# SoC_pwr_1.net
KiCad netlist of a schematic drawn in Altium Designer
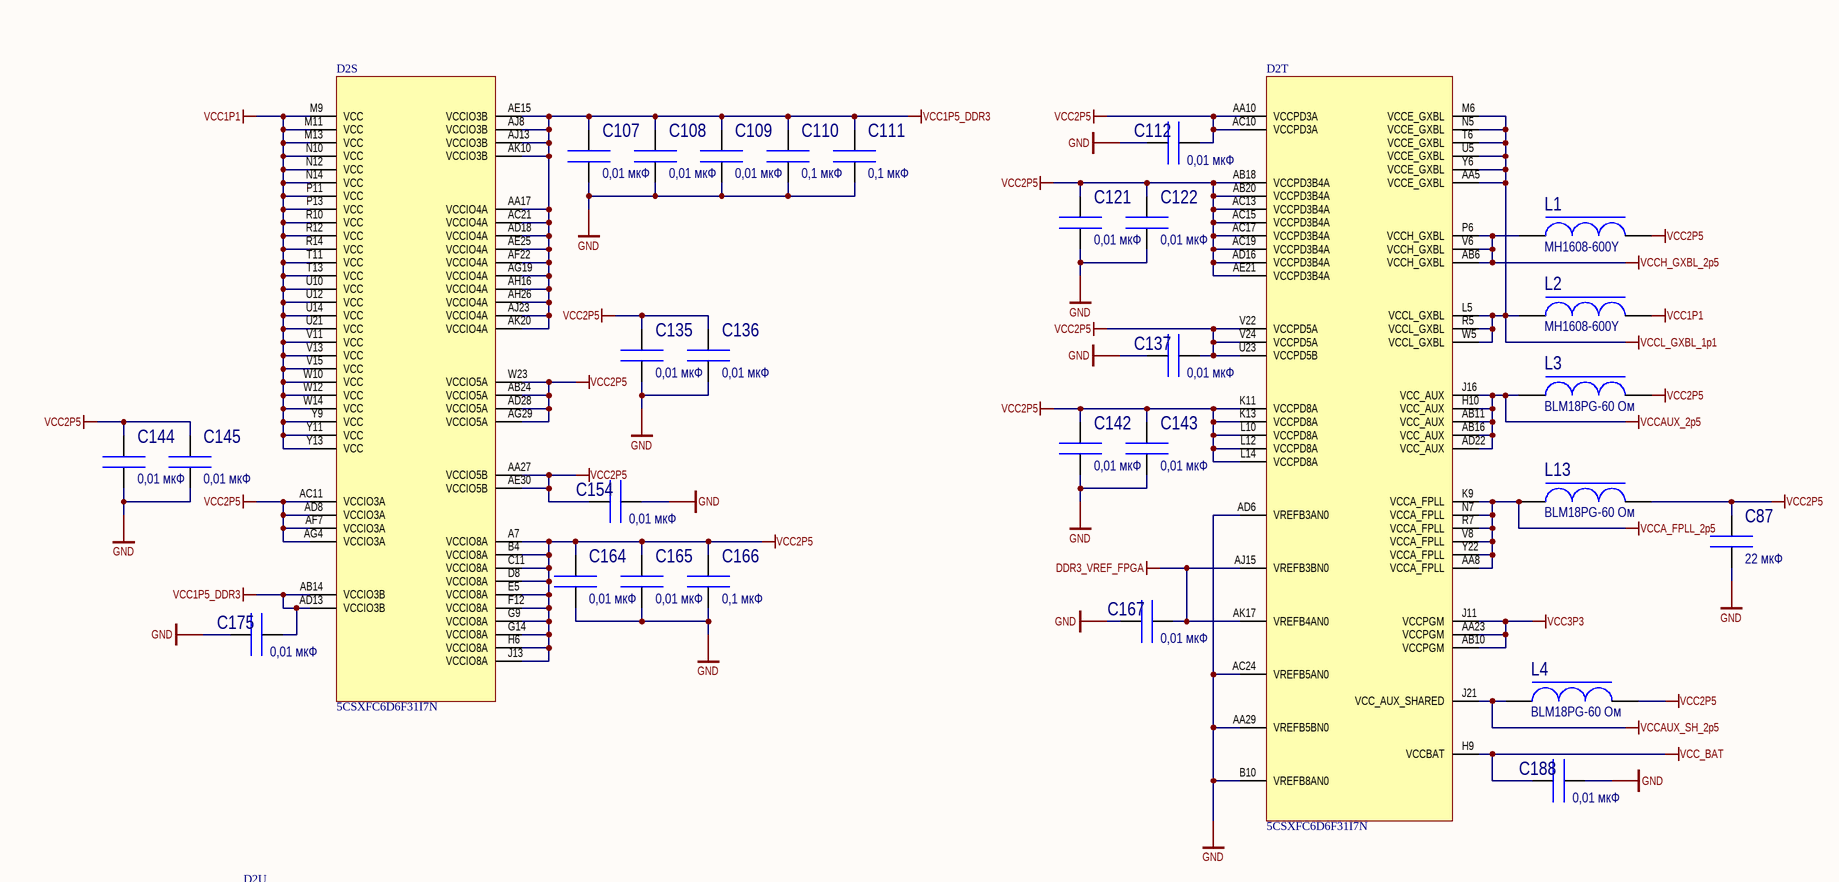
[diagram p0: SoC_pwr_1.SchDoc, top left]
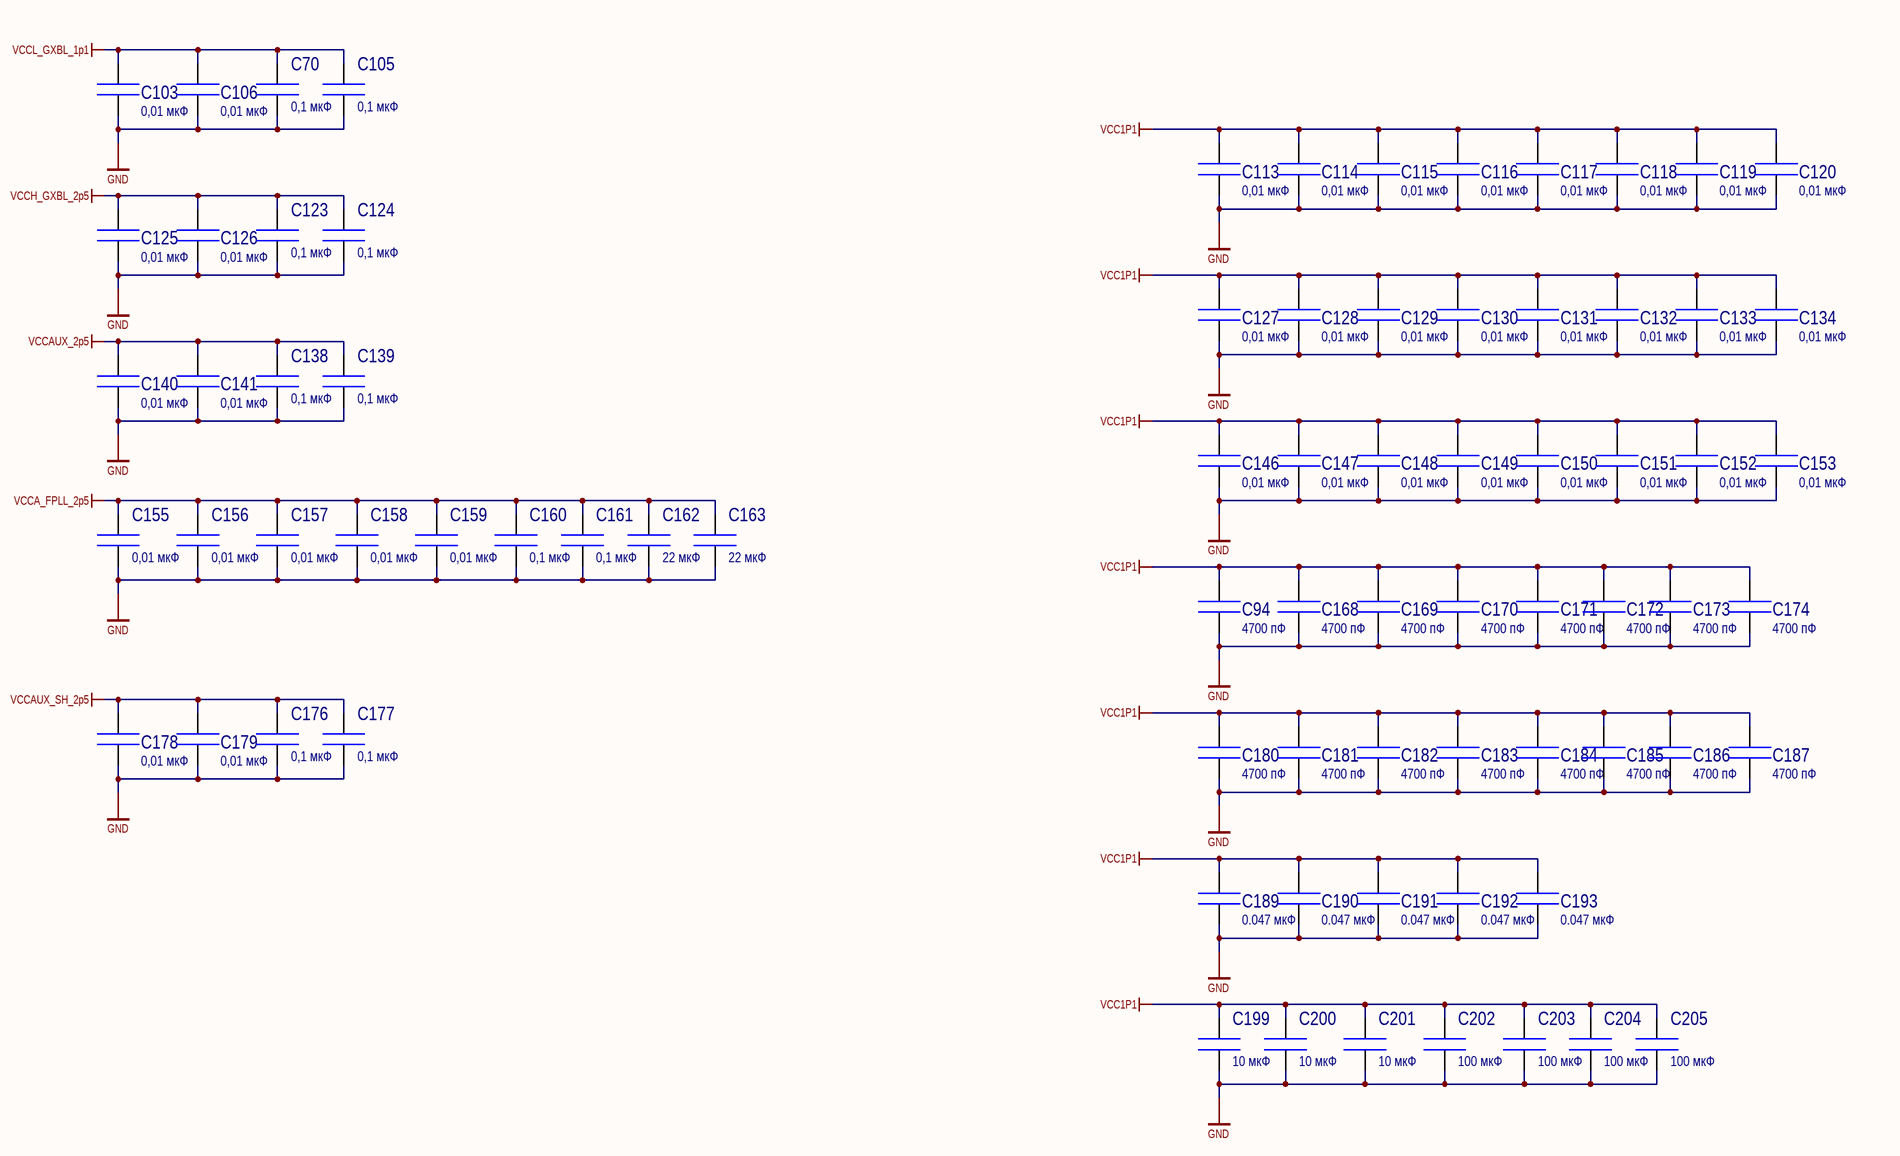
[diagram p1: SoC_pwr_1.SchDoc, top right]
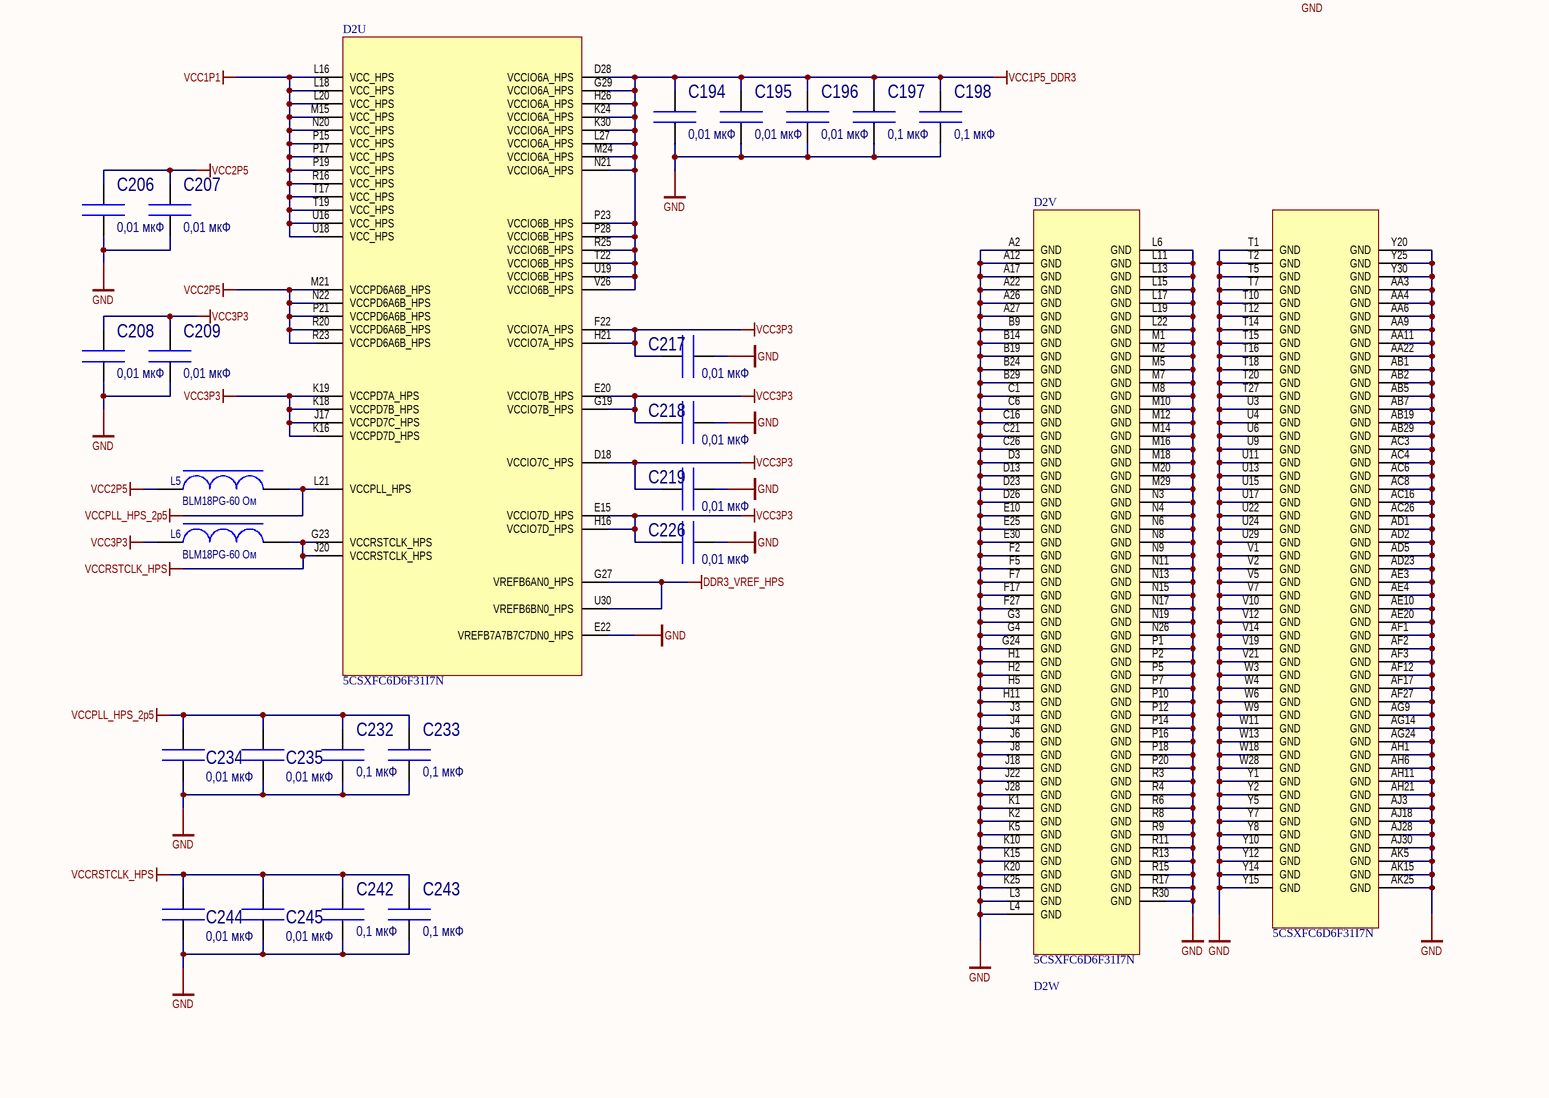
[diagram p2: SoC_pwr_1.SchDoc, bottom left]
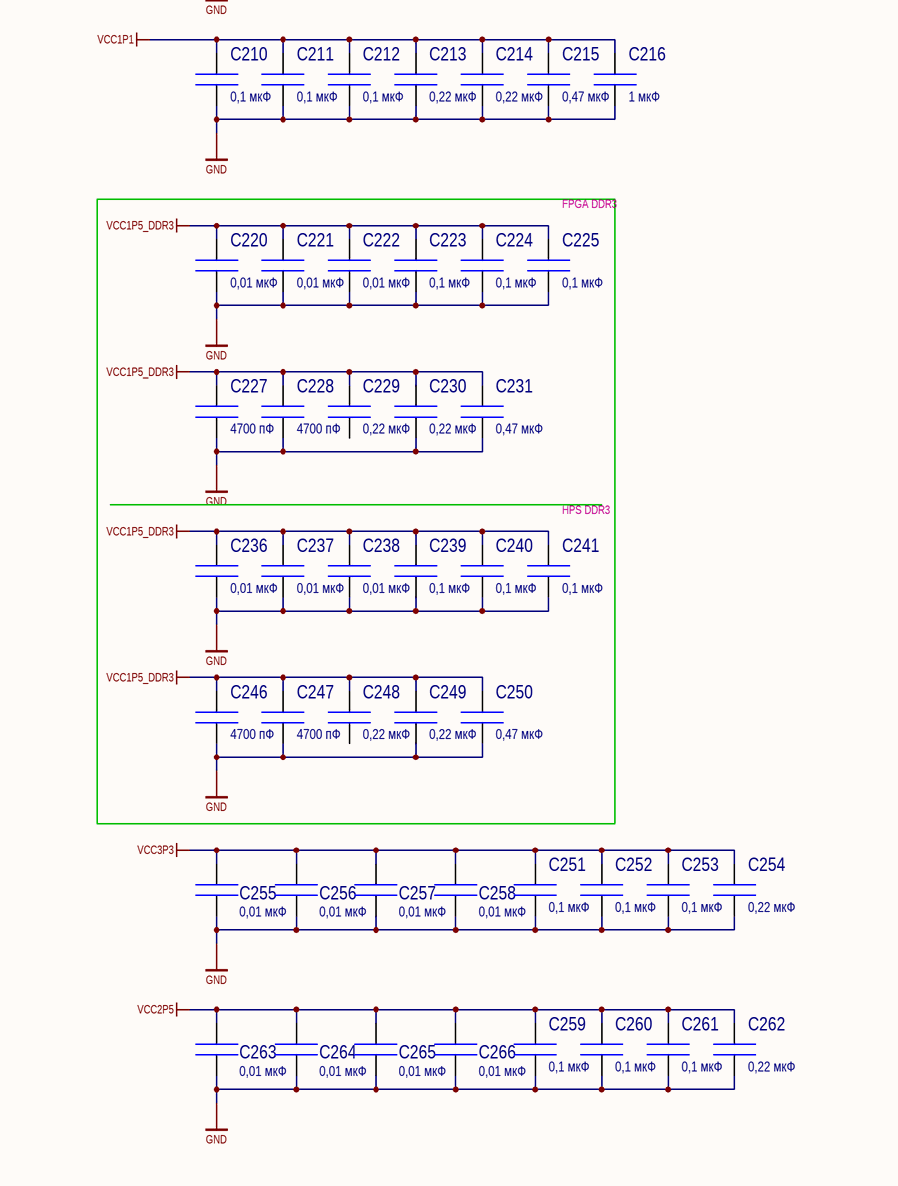
[diagram p3: SoC_pwr_1.SchDoc, bottom right]

(export (version "E")
  (design (tool "Eeschema 10.0.6"))
  (components
    (comp (ref "C70")
      (value "0,1 мкФ")
      (footprint "CC0402(1005)")
      (description "Чип конденсатор керамический")
      (fields (field (name "Comment") "CC0402-X7R-0,1 мкФ-20%-10В"))
      (libsource (lib "Чип конденсаторы") (part "CC0402-X7R-#-20%-10В"))
    )
    (comp (ref "C87")
      (value "22 мкФ")
      (footprint "CC0603")
      (description "Чип конденсатор керамический")
      (fields (field (name "Comment") "CC0603-X5R-22 мкФ-20%-6,3В"))
      (libsource (lib "Конденсаторы") (part "CC0603-X5R-#-20%-6,3В"))
    )
    (comp (ref "C94")
      (value "4700 пФ")
      (footprint "CC0402(1005)")
      (description "Чип конденсатор керамический")
      (fields (field (name "Comment") "CC0402-X7R-4700 пФ-10%-50В"))
      (libsource (lib "Чип конденсаторы") (part "CC0402-X7R-#-20%-10В"))
    )
    (comp (ref "C103")
      (value "0,01 мкФ")
      (footprint "CC0402(1005)")
      (description "Чип конденсатор керамический")
      (fields (field (name "Comment") "CC0402-X7R-0,01 мкФ-10%-50В"))
      (libsource (lib "Чип конденсаторы") (part "CC0402-X7R-#-20%-10В"))
    )
    (comp (ref "C105")
      (value "0,1 мкФ")
      (footprint "CC0402(1005)")
      (description "Чип конденсатор керамический")
      (fields (field (name "Comment") "CC0402-X7R-0,1 мкФ-20%-10В"))
      (libsource (lib "Чип конденсаторы") (part "CC0402-X7R-#-20%-10В"))
    )
    (comp (ref "C106")
      (value "0,01 мкФ")
      (footprint "CC0402(1005)")
      (description "Чип конденсатор керамический")
      (fields (field (name "Comment") "CC0402-X7R-0,01 мкФ-10%-50В"))
      (libsource (lib "Чип конденсаторы") (part "CC0402-X7R-#-20%-10В"))
    )
    (comp (ref "C107")
      (value "0,01 мкФ")
      (footprint "CC0402(1005)")
      (description "Чип конденсатор керамический")
      (fields (field (name "Comment") "CC0402-X7R-0,01 мкФ-10%-50В"))
      (libsource (lib "Чип конденсаторы") (part "CC0402-X7R-#-20%-10В"))
    )
    (comp (ref "C108")
      (value "0,01 мкФ")
      (footprint "CC0402(1005)")
      (description "Чип конденсатор керамический")
      (fields (field (name "Comment") "CC0402-X7R-0,01 мкФ-10%-50В"))
      (libsource (lib "Чип конденсаторы") (part "CC0402-X7R-#-20%-10В"))
    )
    (comp (ref "C109")
      (value "0,01 мкФ")
      (footprint "CC0402(1005)")
      (description "Чип конденсатор керамический")
      (fields (field (name "Comment") "CC0402-X7R-0,01 мкФ-10%-50В"))
      (libsource (lib "Чип конденсаторы") (part "CC0402-X7R-#-20%-10В"))
    )
    (comp (ref "C110")
      (value "0,1 мкФ")
      (footprint "CC0402(1005)")
      (description "Чип конденсатор керамический")
      (fields (field (name "Comment") "CC0402-X7R-0,1 мкФ-20%-10В"))
      (libsource (lib "Чип конденсаторы") (part "CC0402-X7R-#-20%-10В"))
    )
    (comp (ref "C111")
      (value "0,1 мкФ")
      (footprint "CC0402(1005)")
      (description "Чип конденсатор керамический")
      (fields (field (name "Comment") "CC0402-X7R-0,1 мкФ-20%-10В"))
      (libsource (lib "Чип конденсаторы") (part "CC0402-X7R-#-20%-10В"))
    )
    (comp (ref "C112")
      (value "0,01 мкФ")
      (footprint "CC0402(1005)")
      (description "Чип конденсатор керамический")
      (fields (field (name "Comment") "CC0402-X7R-0,01 мкФ-10%-50В"))
      (libsource (lib "Чип конденсаторы") (part "CC0402-X7R-#-20%-10В"))
    )
    (comp (ref "C113")
      (value "0,01 мкФ")
      (footprint "CC0402(1005)")
      (description "Чип конденсатор керамический")
      (fields (field (name "Comment") "CC0402-X7R-0,01 мкФ-10%-50В"))
      (libsource (lib "Чип конденсаторы") (part "CC0402-X7R-#-20%-10В"))
    )
    (comp (ref "C114")
      (value "0,01 мкФ")
      (footprint "CC0402(1005)")
      (description "Чип конденсатор керамический")
      (fields (field (name "Comment") "CC0402-X7R-0,01 мкФ-10%-50В"))
      (libsource (lib "Чип конденсаторы") (part "CC0402-X7R-#-20%-10В"))
    )
    (comp (ref "C115")
      (value "0,01 мкФ")
      (footprint "CC0402(1005)")
      (description "Чип конденсатор керамический")
      (fields (field (name "Comment") "CC0402-X7R-0,01 мкФ-10%-50В"))
      (libsource (lib "Чип конденсаторы") (part "CC0402-X7R-#-20%-10В"))
    )
    (comp (ref "C116")
      (value "0,01 мкФ")
      (footprint "CC0402(1005)")
      (description "Чип конденсатор керамический")
      (fields (field (name "Comment") "CC0402-X7R-0,01 мкФ-10%-50В"))
      (libsource (lib "Чип конденсаторы") (part "CC0402-X7R-#-20%-10В"))
    )
    (comp (ref "C117")
      (value "0,01 мкФ")
      (footprint "CC0402(1005)")
      (description "Чип конденсатор керамический")
      (fields (field (name "Comment") "CC0402-X7R-0,01 мкФ-10%-50В"))
      (libsource (lib "Чип конденсаторы") (part "CC0402-X7R-#-20%-10В"))
    )
    (comp (ref "C118")
      (value "0,01 мкФ")
      (footprint "CC0402(1005)")
      (description "Чип конденсатор керамический")
      (fields (field (name "Comment") "CC0402-X7R-0,01 мкФ-10%-50В"))
      (libsource (lib "Чип конденсаторы") (part "CC0402-X7R-#-20%-10В"))
    )
    (comp (ref "C119")
      (value "0,01 мкФ")
      (footprint "CC0402(1005)")
      (description "Чип конденсатор керамический")
      (fields (field (name "Comment") "CC0402-X7R-0,01 мкФ-10%-50В"))
      (libsource (lib "Чип конденсаторы") (part "CC0402-X7R-#-20%-10В"))
    )
    (comp (ref "C120")
      (value "0,01 мкФ")
      (footprint "CC0402(1005)")
      (description "Чип конденсатор керамический")
      (fields (field (name "Comment") "CC0402-X7R-0,01 мкФ-10%-50В"))
      (libsource (lib "Чип конденсаторы") (part "CC0402-X7R-#-20%-10В"))
    )
    (comp (ref "C121")
      (value "0,01 мкФ")
      (footprint "CC0402(1005)")
      (description "Чип конденсатор керамический")
      (fields (field (name "Comment") "CC0402-X7R-0,01 мкФ-10%-50В"))
      (libsource (lib "Чип конденсаторы") (part "CC0402-X7R-#-20%-10В"))
    )
    (comp (ref "C122")
      (value "0,01 мкФ")
      (footprint "CC0402(1005)")
      (description "Чип конденсатор керамический")
      (fields (field (name "Comment") "CC0402-X7R-0,01 мкФ-10%-50В"))
      (libsource (lib "Чип конденсаторы") (part "CC0402-X7R-#-20%-10В"))
    )
    (comp (ref "C123")
      (value "0,1 мкФ")
      (footprint "CC0402(1005)")
      (description "Чип конденсатор керамический")
      (fields (field (name "Comment") "CC0402-X7R-0,1 мкФ-20%-10В"))
      (libsource (lib "Чип конденсаторы") (part "CC0402-X7R-#-20%-10В"))
    )
    (comp (ref "C124")
      (value "0,1 мкФ")
      (footprint "CC0402(1005)")
      (description "Чип конденсатор керамический")
      (fields (field (name "Comment") "CC0402-X7R-0,1 мкФ-20%-10В"))
      (libsource (lib "Чип конденсаторы") (part "CC0402-X7R-#-20%-10В"))
    )
    (comp (ref "C125")
      (value "0,01 мкФ")
      (footprint "CC0402(1005)")
      (description "Чип конденсатор керамический")
      (fields (field (name "Comment") "CC0402-X7R-0,01 мкФ-10%-50В"))
      (libsource (lib "Чип конденсаторы") (part "CC0402-X7R-#-20%-10В"))
    )
    (comp (ref "C126")
      (value "0,01 мкФ")
      (footprint "CC0402(1005)")
      (description "Чип конденсатор керамический")
      (fields (field (name "Comment") "CC0402-X7R-0,01 мкФ-10%-50В"))
      (libsource (lib "Чип конденсаторы") (part "CC0402-X7R-#-20%-10В"))
    )
    (comp (ref "C127")
      (value "0,01 мкФ")
      (footprint "CC0402(1005)")
      (description "Чип конденсатор керамический")
      (fields (field (name "Comment") "CC0402-X7R-0,01 мкФ-10%-50В"))
      (libsource (lib "Чип конденсаторы") (part "CC0402-X7R-#-20%-10В"))
    )
    (comp (ref "C128")
      (value "0,01 мкФ")
      (footprint "CC0402(1005)")
      (description "Чип конденсатор керамический")
      (fields (field (name "Comment") "CC0402-X7R-0,01 мкФ-10%-50В"))
      (libsource (lib "Чип конденсаторы") (part "CC0402-X7R-#-20%-10В"))
    )
    (comp (ref "C129")
      (value "0,01 мкФ")
      (footprint "CC0402(1005)")
      (description "Чип конденсатор керамический")
      (fields (field (name "Comment") "CC0402-X7R-0,01 мкФ-10%-50В"))
      (libsource (lib "Чип конденсаторы") (part "CC0402-X7R-#-20%-10В"))
    )
    (comp (ref "C130")
      (value "0,01 мкФ")
      (footprint "CC0402(1005)")
      (description "Чип конденсатор керамический")
      (fields (field (name "Comment") "CC0402-X7R-0,01 мкФ-10%-50В"))
      (libsource (lib "Чип конденсаторы") (part "CC0402-X7R-#-20%-10В"))
    )
    (comp (ref "C131")
      (value "0,01 мкФ")
      (footprint "CC0402(1005)")
      (description "Чип конденсатор керамический")
      (fields (field (name "Comment") "CC0402-X7R-0,01 мкФ-10%-50В"))
      (libsource (lib "Чип конденсаторы") (part "CC0402-X7R-#-20%-10В"))
    )
    (comp (ref "C132")
      (value "0,01 мкФ")
      (footprint "CC0402(1005)")
      (description "Чип конденсатор керамический")
      (fields (field (name "Comment") "CC0402-X7R-0,01 мкФ-10%-50В"))
      (libsource (lib "Чип конденсаторы") (part "CC0402-X7R-#-20%-10В"))
    )
    (comp (ref "C133")
      (value "0,01 мкФ")
      (footprint "CC0402(1005)")
      (description "Чип конденсатор керамический")
      (fields (field (name "Comment") "CC0402-X7R-0,01 мкФ-10%-50В"))
      (libsource (lib "Чип конденсаторы") (part "CC0402-X7R-#-20%-10В"))
    )
    (comp (ref "C134")
      (value "0,01 мкФ")
      (footprint "CC0402(1005)")
      (description "Чип конденсатор керамический")
      (fields (field (name "Comment") "CC0402-X7R-0,01 мкФ-10%-50В"))
      (libsource (lib "Чип конденсаторы") (part "CC0402-X7R-#-20%-10В"))
    )
    (comp (ref "C135")
      (value "0,01 мкФ")
      (footprint "CC0402(1005)")
      (description "Чип конденсатор керамический")
      (fields (field (name "Comment") "CC0402-X7R-0,01 мкФ-10%-50В"))
      (libsource (lib "Чип конденсаторы") (part "CC0402-X7R-#-20%-10В"))
    )
    (comp (ref "C136")
      (value "0,01 мкФ")
      (footprint "CC0402(1005)")
      (description "Чип конденсатор керамический")
      (fields (field (name "Comment") "CC0402-X7R-0,01 мкФ-10%-50В"))
      (libsource (lib "Чип конденсаторы") (part "CC0402-X7R-#-20%-10В"))
    )
    (comp (ref "C137")
      (value "0,01 мкФ")
      (footprint "CC0402(1005)")
      (description "Чип конденсатор керамический")
      (fields (field (name "Comment") "CC0402-X7R-0,01 мкФ-10%-50В"))
      (libsource (lib "Чип конденсаторы") (part "CC0402-X7R-#-20%-10В"))
    )
    (comp (ref "C138")
      (value "0,1 мкФ")
      (footprint "CC0402(1005)")
      (description "Чип конденсатор керамический")
      (fields (field (name "Comment") "CC0402-X7R-0,1 мкФ-20%-10В"))
      (libsource (lib "Чип конденсаторы") (part "CC0402-X7R-#-20%-10В"))
    )
    (comp (ref "C139")
      (value "0,1 мкФ")
      (footprint "CC0402(1005)")
      (description "Чип конденсатор керамический")
      (fields (field (name "Comment") "CC0402-X7R-0,1 мкФ-20%-10В"))
      (libsource (lib "Чип конденсаторы") (part "CC0402-X7R-#-20%-10В"))
    )
    (comp (ref "C140")
      (value "0,01 мкФ")
      (footprint "CC0402(1005)")
      (description "Чип конденсатор керамический")
      (fields (field (name "Comment") "CC0402-X7R-0,01 мкФ-10%-50В"))
      (libsource (lib "Чип конденсаторы") (part "CC0402-X7R-#-20%-10В"))
    )
    (comp (ref "C141")
      (value "0,01 мкФ")
      (footprint "CC0402(1005)")
      (description "Чип конденсатор керамический")
      (fields (field (name "Comment") "CC0402-X7R-0,01 мкФ-10%-50В"))
      (libsource (lib "Чип конденсаторы") (part "CC0402-X7R-#-20%-10В"))
    )
    (comp (ref "C142")
      (value "0,01 мкФ")
      (footprint "CC0402(1005)")
      (description "Чип конденсатор керамический")
      (fields (field (name "Comment") "CC0402-X7R-0,01 мкФ-10%-50В"))
      (libsource (lib "Чип конденсаторы") (part "CC0402-X7R-#-20%-10В"))
    )
    (comp (ref "C143")
      (value "0,01 мкФ")
      (footprint "CC0402(1005)")
      (description "Чип конденсатор керамический")
      (fields (field (name "Comment") "CC0402-X7R-0,01 мкФ-10%-50В"))
      (libsource (lib "Чип конденсаторы") (part "CC0402-X7R-#-20%-10В"))
    )
    (comp (ref "C144")
      (value "0,01 мкФ")
      (footprint "CC0402(1005)")
      (description "Чип конденсатор керамический")
      (fields (field (name "Comment") "CC0402-X7R-0,01 мкФ-10%-50В"))
      (libsource (lib "Чип конденсаторы") (part "CC0402-X7R-#-20%-10В"))
    )
    (comp (ref "C145")
      (value "0,01 мкФ")
      (footprint "CC0402(1005)")
      (description "Чип конденсатор керамический")
      (fields (field (name "Comment") "CC0402-X7R-0,01 мкФ-10%-50В"))
      (libsource (lib "Чип конденсаторы") (part "CC0402-X7R-#-20%-10В"))
    )
    (comp (ref "C146")
      (value "0,01 мкФ")
      (footprint "CC0402(1005)")
      (description "Чип конденсатор керамический")
      (fields (field (name "Comment") "CC0402-X7R-0,01 мкФ-10%-50В"))
      (libsource (lib "Чип конденсаторы") (part "CC0402-X7R-#-20%-10В"))
    )
    (comp (ref "C147")
      (value "0,01 мкФ")
      (footprint "CC0402(1005)")
      (description "Чип конденсатор керамический")
      (fields (field (name "Comment") "CC0402-X7R-0,01 мкФ-10%-50В"))
      (libsource (lib "Чип конденсаторы") (part "CC0402-X7R-#-20%-10В"))
    )
    (comp (ref "C148")
      (value "0,01 мкФ")
      (footprint "CC0402(1005)")
      (description "Чип конденсатор керамический")
      (fields (field (name "Comment") "CC0402-X7R-0,01 мкФ-10%-50В"))
      (libsource (lib "Чип конденсаторы") (part "CC0402-X7R-#-20%-10В"))
    )
    (comp (ref "C149")
      (value "0,01 мкФ")
      (footprint "CC0402(1005)")
      (description "Чип конденсатор керамический")
      (fields (field (name "Comment") "CC0402-X7R-0,01 мкФ-10%-50В"))
      (libsource (lib "Чип конденсаторы") (part "CC0402-X7R-#-20%-10В"))
    )
    (comp (ref "C150")
      (value "0,01 мкФ")
      (footprint "CC0402(1005)")
      (description "Чип конденсатор керамический")
      (fields (field (name "Comment") "CC0402-X7R-0,01 мкФ-10%-50В"))
      (libsource (lib "Чип конденсаторы") (part "CC0402-X7R-#-20%-10В"))
    )
    (comp (ref "C151")
      (value "0,01 мкФ")
      (footprint "CC0402(1005)")
      (description "Чип конденсатор керамический")
      (fields (field (name "Comment") "CC0402-X7R-0,01 мкФ-10%-50В"))
      (libsource (lib "Чип конденсаторы") (part "CC0402-X7R-#-20%-10В"))
    )
    (comp (ref "C152")
      (value "0,01 мкФ")
      (footprint "CC0402(1005)")
      (description "Чип конденсатор керамический")
      (fields (field (name "Comment") "CC0402-X7R-0,01 мкФ-10%-50В"))
      (libsource (lib "Чип конденсаторы") (part "CC0402-X7R-#-20%-10В"))
    )
    (comp (ref "C153")
      (value "0,01 мкФ")
      (footprint "CC0402(1005)")
      (description "Чип конденсатор керамический")
      (fields (field (name "Comment") "CC0402-X7R-0,01 мкФ-10%-50В"))
      (libsource (lib "Чип конденсаторы") (part "CC0402-X7R-#-20%-10В"))
    )
    (comp (ref "C154")
      (value "0,01 мкФ")
      (footprint "CC0402(1005)")
      (description "Чип конденсатор керамический")
      (fields (field (name "Comment") "CC0402-X7R-0,01 мкФ-10%-50В"))
      (libsource (lib "Чип конденсаторы") (part "CC0402-X7R-#-20%-10В"))
    )
    (comp (ref "C155")
      (value "0,01 мкФ")
      (footprint "CC0402(1005)")
      (description "Чип конденсатор керамический")
      (fields (field (name "Comment") "CC0402-X7R-0,01 мкФ-10%-50В"))
      (libsource (lib "Чип конденсаторы") (part "CC0402-X7R-#-20%-10В"))
    )
    (comp (ref "C156")
      (value "0,01 мкФ")
      (footprint "CC0402(1005)")
      (description "Чип конденсатор керамический")
      (fields (field (name "Comment") "CC0402-X7R-0,01 мкФ-10%-50В"))
      (libsource (lib "Чип конденсаторы") (part "CC0402-X7R-#-20%-10В"))
    )
    (comp (ref "C157")
      (value "0,01 мкФ")
      (footprint "CC0402(1005)")
      (description "Чип конденсатор керамический")
      (fields (field (name "Comment") "CC0402-X7R-0,01 мкФ-10%-50В"))
      (libsource (lib "Чип конденсаторы") (part "CC0402-X7R-#-20%-10В"))
    )
    (comp (ref "C158")
      (value "0,01 мкФ")
      (footprint "CC0402(1005)")
      (description "Чип конденсатор керамический")
      (fields (field (name "Comment") "CC0402-X7R-0,01 мкФ-10%-50В"))
      (libsource (lib "Чип конденсаторы") (part "CC0402-X7R-#-20%-10В"))
    )
    (comp (ref "C159")
      (value "0,01 мкФ")
      (footprint "CC0402(1005)")
      (description "Чип конденсатор керамический")
      (fields (field (name "Comment") "CC0402-X7R-0,01 мкФ-10%-50В"))
      (libsource (lib "Чип конденсаторы") (part "CC0402-X7R-#-20%-10В"))
    )
    (comp (ref "C160")
      (value "0,1 мкФ")
      (footprint "CC0402(1005)")
      (description "Чип конденсатор керамический")
      (fields (field (name "Comment") "CC0402-X7R-0,1 мкФ-20%-10В"))
      (libsource (lib "Чип конденсаторы") (part "CC0402-X7R-#-20%-10В"))
    )
    (comp (ref "C161")
      (value "0,1 мкФ")
      (footprint "CC0402(1005)")
      (description "Чип конденсатор керамический")
      (fields (field (name "Comment") "CC0402-X7R-0,1 мкФ-20%-10В"))
      (libsource (lib "Чип конденсаторы") (part "CC0402-X7R-#-20%-10В"))
    )
    (comp (ref "C162")
      (value "22 мкФ")
      (footprint "CC0603")
      (description "Чип конденсатор керамический")
      (fields (field (name "Comment") "CC0603-X5R-22 мкФ-20%-6,3В"))
      (libsource (lib "Конденсаторы") (part "CC0603-X5R-#-20%-6,3В"))
    )
    (comp (ref "C163")
      (value "22 мкФ")
      (footprint "CC0603")
      (description "Чип конденсатор керамический")
      (fields (field (name "Comment") "CC0603-X5R-22 мкФ-20%-6,3В"))
      (libsource (lib "Конденсаторы") (part "CC0603-X5R-#-20%-6,3В"))
    )
    (comp (ref "C164")
      (value "0,01 мкФ")
      (footprint "CC0402(1005)")
      (description "Чип конденсатор керамический")
      (fields (field (name "Comment") "CC0402-X7R-0,01 мкФ-10%-50В"))
      (libsource (lib "Чип конденсаторы") (part "CC0402-X7R-#-20%-10В"))
    )
    (comp (ref "C165")
      (value "0,01 мкФ")
      (footprint "CC0402(1005)")
      (description "Чип конденсатор керамический")
      (fields (field (name "Comment") "CC0402-X7R-0,01 мкФ-10%-50В"))
      (libsource (lib "Чип конденсаторы") (part "CC0402-X7R-#-20%-10В"))
    )
    (comp (ref "C166")
      (value "0,1 мкФ")
      (footprint "CC0402(1005)")
      (description "Чип конденсатор керамический")
      (fields (field (name "Comment") "CC0402-X7R-0,1 мкФ-20%-10В"))
      (libsource (lib "Чип конденсаторы") (part "CC0402-X7R-#-20%-10В"))
    )
    (comp (ref "C167")
      (value "0,01 мкФ")
      (footprint "CC0402(1005)")
      (description "Чип конденсатор керамический")
      (fields (field (name "Comment") "CC0402-X7R-0,01 мкФ-10%-50В"))
      (libsource (lib "Чип конденсаторы") (part "CC0402-X7R-#-20%-10В"))
    )
    (comp (ref "C168")
      (value "4700 пФ")
      (footprint "CC0402(1005)")
      (description "Чип конденсатор керамический")
      (fields (field (name "Comment") "CC0402-X7R-4700 пФ-10%-50В"))
      (libsource (lib "Чип конденсаторы") (part "CC0402-X7R-#-20%-10В"))
    )
    (comp (ref "C169")
      (value "4700 пФ")
      (footprint "CC0402(1005)")
      (description "Чип конденсатор керамический")
      (fields (field (name "Comment") "CC0402-X7R-4700 пФ-10%-50В"))
      (libsource (lib "Чип конденсаторы") (part "CC0402-X7R-#-20%-10В"))
    )
    (comp (ref "C170")
      (value "4700 пФ")
      (footprint "CC0402(1005)")
      (description "Чип конденсатор керамический")
      (fields (field (name "Comment") "CC0402-X7R-4700 пФ-10%-50В"))
      (libsource (lib "Чип конденсаторы") (part "CC0402-X7R-#-20%-10В"))
    )
    (comp (ref "C171")
      (value "4700 пФ")
      (footprint "CC0402(1005)")
      (description "Чип конденсатор керамический")
      (fields (field (name "Comment") "CC0402-X7R-4700 пФ-10%-50В"))
      (libsource (lib "Чип конденсаторы") (part "CC0402-X7R-#-20%-10В"))
    )
    (comp (ref "C172")
      (value "4700 пФ")
      (footprint "CC0402(1005)")
      (description "Чип конденсатор керамический")
      (fields (field (name "Comment") "CC0402-X7R-4700 пФ-10%-50В"))
      (libsource (lib "Чип конденсаторы") (part "CC0402-X7R-#-20%-10В"))
    )
    (comp (ref "C173")
      (value "4700 пФ")
      (footprint "CC0402(1005)")
      (description "Чип конденсатор керамический")
      (fields (field (name "Comment") "CC0402-X7R-4700 пФ-10%-50В"))
      (libsource (lib "Чип конденсаторы") (part "CC0402-X7R-#-20%-10В"))
    )
    (comp (ref "C174")
      (value "4700 пФ")
      (footprint "CC0402(1005)")
      (description "Чип конденсатор керамический")
      (fields (field (name "Comment") "CC0402-X7R-4700 пФ-10%-50В"))
      (libsource (lib "Чип конденсаторы") (part "CC0402-X7R-#-20%-10В"))
    )
    (comp (ref "C175")
      (value "0,01 мкФ")
      (footprint "CC0402(1005)")
      (description "Чип конденсатор керамический")
      (fields (field (name "Comment") "CC0402-X7R-0,01 мкФ-10%-50В"))
      (libsource (lib "Чип конденсаторы") (part "CC0402-X7R-#-20%-10В"))
    )
    (comp (ref "C176")
      (value "0,1 мкФ")
      (footprint "CC0402(1005)")
      (description "Чип конденсатор керамический")
      (fields (field (name "Comment") "CC0402-X7R-0,1 мкФ-20%-10В"))
      (libsource (lib "Чип конденсаторы") (part "CC0402-X7R-#-20%-10В"))
    )
    (comp (ref "C177")
      (value "0,1 мкФ")
      (footprint "CC0402(1005)")
      (description "Чип конденсатор керамический")
      (fields (field (name "Comment") "CC0402-X7R-0,1 мкФ-20%-10В"))
      (libsource (lib "Чип конденсаторы") (part "CC0402-X7R-#-20%-10В"))
    )
    (comp (ref "C178")
      (value "0,01 мкФ")
      (footprint "CC0402(1005)")
      (description "Чип конденсатор керамический")
      (fields (field (name "Comment") "CC0402-X7R-0,01 мкФ-10%-50В"))
      (libsource (lib "Чип конденсаторы") (part "CC0402-X7R-#-20%-10В"))
    )
    (comp (ref "C179")
      (value "0,01 мкФ")
      (footprint "CC0402(1005)")
      (description "Чип конденсатор керамический")
      (fields (field (name "Comment") "CC0402-X7R-0,01 мкФ-10%-50В"))
      (libsource (lib "Чип конденсаторы") (part "CC0402-X7R-#-20%-10В"))
    )
    (comp (ref "C180")
      (value "4700 пФ")
      (footprint "CC0402(1005)")
      (description "Чип конденсатор керамический")
      (fields (field (name "Comment") "CC0402-X7R-4700 пФ-10%-50В"))
      (libsource (lib "Чип конденсаторы") (part "CC0402-X7R-#-20%-10В"))
    )
    (comp (ref "C181")
      (value "4700 пФ")
      (footprint "CC0402(1005)")
      (description "Чип конденсатор керамический")
      (fields (field (name "Comment") "CC0402-X7R-4700 пФ-10%-50В"))
      (libsource (lib "Чип конденсаторы") (part "CC0402-X7R-#-20%-10В"))
    )
    (comp (ref "C182")
      (value "4700 пФ")
      (footprint "CC0402(1005)")
      (description "Чип конденсатор керамический")
      (fields (field (name "Comment") "CC0402-X7R-4700 пФ-10%-50В"))
      (libsource (lib "Чип конденсаторы") (part "CC0402-X7R-#-20%-10В"))
    )
    (comp (ref "C183")
      (value "4700 пФ")
      (footprint "CC0402(1005)")
      (description "Чип конденсатор керамический")
      (fields (field (name "Comment") "CC0402-X7R-4700 пФ-10%-50В"))
      (libsource (lib "Чип конденсаторы") (part "CC0402-X7R-#-20%-10В"))
    )
    (comp (ref "C184")
      (value "4700 пФ")
      (footprint "CC0402(1005)")
      (description "Чип конденсатор керамический")
      (fields (field (name "Comment") "CC0402-X7R-4700 пФ-10%-50В"))
      (libsource (lib "Чип конденсаторы") (part "CC0402-X7R-#-20%-10В"))
    )
    (comp (ref "C185")
      (value "4700 пФ")
      (footprint "CC0402(1005)")
      (description "Чип конденсатор керамический")
      (fields (field (name "Comment") "CC0402-X7R-4700 пФ-10%-50В"))
      (libsource (lib "Чип конденсаторы") (part "CC0402-X7R-#-20%-10В"))
    )
    (comp (ref "C186")
      (value "4700 пФ")
      (footprint "CC0402(1005)")
      (description "Чип конденсатор керамический")
      (fields (field (name "Comment") "CC0402-X7R-4700 пФ-10%-50В"))
      (libsource (lib "Чип конденсаторы") (part "CC0402-X7R-#-20%-10В"))
    )
    (comp (ref "C187")
      (value "4700 пФ")
      (footprint "CC0402(1005)")
      (description "Чип конденсатор керамический")
      (fields (field (name "Comment") "CC0402-X7R-4700 пФ-10%-50В"))
      (libsource (lib "Чип конденсаторы") (part "CC0402-X7R-#-20%-10В"))
    )
    (comp (ref "C188")
      (value "0,01 мкФ")
      (footprint "CC0402(1005)")
      (description "Чип конденсатор керамический")
      (fields (field (name "Comment") "CC0402-X7R-0,01 мкФ-10%-50В"))
      (libsource (lib "Чип конденсаторы") (part "CC0402-X7R-#-20%-10В"))
    )
    (comp (ref "C189")
      (value "0.047 мкФ")
      (footprint "CC0402(1005)")
      (description "Чип конденсатор керамический")
      (fields (field (name "Comment") "CC0402-X7R-0.047 мкФ-10%-50В"))
      (libsource (lib "Чип конденсаторы") (part "CC0402-X7R-#-20%-10В"))
    )
    (comp (ref "C190")
      (value "0.047 мкФ")
      (footprint "CC0402(1005)")
      (description "Чип конденсатор керамический")
      (fields (field (name "Comment") "CC0402-X7R-0.047 мкФ-10%-50В"))
      (libsource (lib "Чип конденсаторы") (part "CC0402-X7R-#-20%-10В"))
    )
    (comp (ref "C191")
      (value "0.047 мкФ")
      (footprint "CC0402(1005)")
      (description "Чип конденсатор керамический")
      (fields (field (name "Comment") "CC0402-X7R-0.047 мкФ-10%-50В"))
      (libsource (lib "Чип конденсаторы") (part "CC0402-X7R-#-20%-10В"))
    )
    (comp (ref "C192")
      (value "0.047 мкФ")
      (footprint "CC0402(1005)")
      (description "Чип конденсатор керамический")
      (fields (field (name "Comment") "CC0402-X7R-0.047 мкФ-10%-50В"))
      (libsource (lib "Чип конденсаторы") (part "CC0402-X7R-#-20%-10В"))
    )
    (comp (ref "C193")
      (value "0.047 мкФ")
      (footprint "CC0402(1005)")
      (description "Чип конденсатор керамический")
      (fields (field (name "Comment") "CC0402-X7R-0.047 мкФ-10%-50В"))
      (libsource (lib "Чип конденсаторы") (part "CC0402-X7R-#-20%-10В"))
    )
    (comp (ref "C194")
      (value "0,01 мкФ")
      (footprint "CC0402(1005)")
      (description "Чип конденсатор керамический")
      (fields (field (name "Comment") "CC0402-X7R-0,01 мкФ-10%-50В"))
      (libsource (lib "Чип конденсаторы") (part "CC0402-X7R-#-20%-10В"))
    )
    (comp (ref "C195")
      (value "0,01 мкФ")
      (footprint "CC0402(1005)")
      (description "Чип конденсатор керамический")
      (fields (field (name "Comment") "CC0402-X7R-0,01 мкФ-10%-50В"))
      (libsource (lib "Чип конденсаторы") (part "CC0402-X7R-#-20%-10В"))
    )
    (comp (ref "C196")
      (value "0,01 мкФ")
      (footprint "CC0402(1005)")
      (description "Чип конденсатор керамический")
      (fields (field (name "Comment") "CC0402-X7R-0,01 мкФ-10%-50В"))
      (libsource (lib "Чип конденсаторы") (part "CC0402-X7R-#-20%-10В"))
    )
    (comp (ref "C197")
      (value "0,1 мкФ")
      (footprint "CC0402(1005)")
      (description "Чип конденсатор керамический")
      (fields (field (name "Comment") "CC0402-X7R-0,1 мкФ-20%-10В"))
      (libsource (lib "Чип конденсаторы") (part "CC0402-X7R-#-20%-10В"))
    )
    (comp (ref "C198")
      (value "0,1 мкФ")
      (footprint "CC0402(1005)")
      (description "Чип конденсатор керамический")
      (fields (field (name "Comment") "CC0402-X7R-0,1 мкФ-20%-10В"))
      (libsource (lib "Чип конденсаторы") (part "CC0402-X7R-#-20%-10В"))
    )
    (comp (ref "C199")
      (value "10 мкФ")
      (footprint "CC0402(1005)")
      (description "Чип конденсатор керамический")
      (fields (field (name "Comment") "CC0402-X5R-10 мкФ-20%-6.3В"))
      (libsource (lib "Чип конденсаторы") (part "CC0402-X7R-#-20%-10В"))
    )
    (comp (ref "C200")
      (value "10 мкФ")
      (footprint "CC0402(1005)")
      (description "Чип конденсатор керамический")
      (fields (field (name "Comment") "CC0402-X5R-10 мкФ-20%-6.3В"))
      (libsource (lib "Чип конденсаторы") (part "CC0402-X7R-#-20%-10В"))
    )
    (comp (ref "C201")
      (value "10 мкФ")
      (footprint "CC0402(1005)")
      (description "Чип конденсатор керамический")
      (fields (field (name "Comment") "CC0402-X5R-10 мкФ-20%-6.3В"))
      (libsource (lib "Чип конденсаторы") (part "CC0402-X7R-#-20%-10В"))
    )
    (comp (ref "C202")
      (value "100 мкФ")
      (footprint "CC0805")
      (description "Чип конденсатор керамический")
      (fields (field (name "Comment") "CC0805-X5R-100 мкФ-20%-4В"))
      (libsource (lib "Конденсаторы") (part "CC0805-X7R-#-20%-25В"))
    )
    (comp (ref "C203")
      (value "100 мкФ")
      (footprint "CC0805")
      (description "Чип конденсатор керамический")
      (fields (field (name "Comment") "CC0805-X5R-100 мкФ-20%-4В"))
      (libsource (lib "Конденсаторы") (part "CC0805-X7R-#-20%-25В"))
    )
    (comp (ref "C204")
      (value "100 мкФ")
      (footprint "CC0805")
      (description "Чип конденсатор керамический")
      (fields (field (name "Comment") "CC0805-X5R-100 мкФ-20%-4В"))
      (libsource (lib "Конденсаторы") (part "CC0805-X7R-#-20%-25В"))
    )
    (comp (ref "C205")
      (value "100 мкФ")
      (footprint "CC0805")
      (description "Чип конденсатор керамический")
      (fields (field (name "Comment") "CC0805-X5R-100 мкФ-20%-4В"))
      (libsource (lib "Конденсаторы") (part "CC0805-X7R-#-20%-25В"))
    )
    (comp (ref "C206")
      (value "0,01 мкФ")
      (footprint "CC0402(1005)")
      (description "Чип конденсатор керамический")
      (fields (field (name "Comment") "CC0402-X7R-0,01 мкФ-10%-50В"))
      (libsource (lib "Чип конденсаторы") (part "CC0402-X7R-#-20%-10В"))
    )
    (comp (ref "C207")
      (value "0,01 мкФ")
      (footprint "CC0402(1005)")
      (description "Чип конденсатор керамический")
      (fields (field (name "Comment") "CC0402-X7R-0,01 мкФ-10%-50В"))
      (libsource (lib "Чип конденсаторы") (part "CC0402-X7R-#-20%-10В"))
    )
    (comp (ref "C208")
      (value "0,01 мкФ")
      (footprint "CC0402(1005)")
      (description "Чип конденсатор керамический")
      (fields (field (name "Comment") "CC0402-X7R-0,01 мкФ-10%-50В"))
      (libsource (lib "Чип конденсаторы") (part "CC0402-X7R-#-20%-10В"))
    )
    (comp (ref "C209")
      (value "0,01 мкФ")
      (footprint "CC0402(1005)")
      (description "Чип конденсатор керамический")
      (fields (field (name "Comment") "CC0402-X7R-0,01 мкФ-10%-50В"))
      (libsource (lib "Чип конденсаторы") (part "CC0402-X7R-#-20%-10В"))
    )
    (comp (ref "C210")
      (value "0,1 мкФ")
      (footprint "CC0402(1005)")
      (description "Чип конденсатор керамический")
      (fields (field (name "Comment") "CC0402-X7R-0,1 мкФ-20%-10В"))
      (libsource (lib "Чип конденсаторы") (part "CC0402-X7R-#-20%-10В"))
    )
    (comp (ref "C211")
      (value "0,1 мкФ")
      (footprint "CC0402(1005)")
      (description "Чип конденсатор керамический")
      (fields (field (name "Comment") "CC0402-X7R-0,1 мкФ-20%-10В"))
      (libsource (lib "Чип конденсаторы") (part "CC0402-X7R-#-20%-10В"))
    )
    (comp (ref "C212")
      (value "0,1 мкФ")
      (footprint "CC0402(1005)")
      (description "Чип конденсатор керамический")
      (fields (field (name "Comment") "CC0402-X7R-0,1 мкФ-20%-10В"))
      (libsource (lib "Чип конденсаторы") (part "CC0402-X7R-#-20%-10В"))
    )
    (comp (ref "C213")
      (value "0,22 мкФ")
      (footprint "CC0402(1005)")
      (description "Чип конденсатор керамический")
      (fields (field (name "Comment") "CC0402-X7R-0,22 мкФ-10%-6.3В"))
      (libsource (lib "Чип конденсаторы") (part "CC0402-X7R-#-20%-10В"))
    )
    (comp (ref "C214")
      (value "0,22 мкФ")
      (footprint "CC0402(1005)")
      (description "Чип конденсатор керамический")
      (fields (field (name "Comment") "CC0402-X7R-0,22 мкФ-10%-6.3В"))
      (libsource (lib "Чип конденсаторы") (part "CC0402-X7R-#-20%-10В"))
    )
    (comp (ref "C215")
      (value "0,47 мкФ")
      (footprint "CC0402(1005)")
      (description "Чип конденсатор керамический")
      (fields (field (name "Comment") "CC0402-X7R-0,47 мкФ-10%-6.3В"))
      (libsource (lib "Чип конденсаторы") (part "CC0402-X7R-#-20%-10В"))
    )
    (comp (ref "C216")
      (value "1 мкФ")
      (footprint "CC0402(1005)")
      (description "Чип конденсатор керамический")
      (fields (field (name "Comment") "CC0402-X5R-1 мкФ-10%-6.3В"))
      (libsource (lib "Чип конденсаторы") (part "CC0402-X7R-#-20%-10В"))
    )
    (comp (ref "C217")
      (value "0,01 мкФ")
      (footprint "CC0402(1005)")
      (description "Чип конденсатор керамический")
      (fields (field (name "Comment") "CC0402-X7R-0,01 мкФ-10%-50В"))
      (libsource (lib "Чип конденсаторы") (part "CC0402-X7R-#-20%-10В"))
    )
    (comp (ref "C218")
      (value "0,01 мкФ")
      (footprint "CC0402(1005)")
      (description "Чип конденсатор керамический")
      (fields (field (name "Comment") "CC0402-X7R-0,01 мкФ-10%-50В"))
      (libsource (lib "Чип конденсаторы") (part "CC0402-X7R-#-20%-10В"))
    )
    (comp (ref "C219")
      (value "0,01 мкФ")
      (footprint "CC0402(1005)")
      (description "Чип конденсатор керамический")
      (fields (field (name "Comment") "CC0402-X7R-0,01 мкФ-10%-50В"))
      (libsource (lib "Чип конденсаторы") (part "CC0402-X7R-#-20%-10В"))
    )
    (comp (ref "C220")
      (value "0,01 мкФ")
      (footprint "CC0402(1005)")
      (description "Чип конденсатор керамический")
      (fields (field (name "Comment") "CC0402-X7R-0,01 мкФ-10%-50В"))
      (libsource (lib "Чип конденсаторы") (part "CC0402-X7R-#-20%-10В"))
    )
    (comp (ref "C221")
      (value "0,01 мкФ")
      (footprint "CC0402(1005)")
      (description "Чип конденсатор керамический")
      (fields (field (name "Comment") "CC0402-X7R-0,01 мкФ-10%-50В"))
      (libsource (lib "Чип конденсаторы") (part "CC0402-X7R-#-20%-10В"))
    )
    (comp (ref "C222")
      (value "0,01 мкФ")
      (footprint "CC0402(1005)")
      (description "Чип конденсатор керамический")
      (fields (field (name "Comment") "CC0402-X7R-0,01 мкФ-10%-50В"))
      (libsource (lib "Чип конденсаторы") (part "CC0402-X7R-#-20%-10В"))
    )
    (comp (ref "C223")
      (value "0,1 мкФ")
      (footprint "CC0402(1005)")
      (description "Чип конденсатор керамический")
      (fields (field (name "Comment") "CC0402-X7R-0,1 мкФ-20%-10В"))
      (libsource (lib "Чип конденсаторы") (part "CC0402-X7R-#-20%-10В"))
    )
    (comp (ref "C224")
      (value "0,1 мкФ")
      (footprint "CC0402(1005)")
      (description "Чип конденсатор керамический")
      (fields (field (name "Comment") "CC0402-X7R-0,1 мкФ-20%-10В"))
      (libsource (lib "Чип конденсаторы") (part "CC0402-X7R-#-20%-10В"))
    )
    (comp (ref "C225")
      (value "0,1 мкФ")
      (footprint "CC0402(1005)")
      (description "Чип конденсатор керамический")
      (fields (field (name "Comment") "CC0402-X7R-0,1 мкФ-20%-10В"))
      (libsource (lib "Чип конденсаторы") (part "CC0402-X7R-#-20%-10В"))
    )
    (comp (ref "C226")
      (value "0,01 мкФ")
      (footprint "CC0402(1005)")
      (description "Чип конденсатор керамический")
      (fields (field (name "Comment") "CC0402-X7R-0,01 мкФ-10%-50В"))
      (libsource (lib "Чип конденсаторы") (part "CC0402-X7R-#-20%-10В"))
    )
    (comp (ref "C227")
      (value "4700 пФ")
      (footprint "CC0402(1005)")
      (description "Чип конденсатор керамический")
      (fields (field (name "Comment") "CC0402-X7R-4700 пФ-10%-50В"))
      (libsource (lib "Чип конденсаторы") (part "CC0402-X7R-#-20%-10В"))
    )
    (comp (ref "C228")
      (value "4700 пФ")
      (footprint "CC0402(1005)")
      (description "Чип конденсатор керамический")
      (fields (field (name "Comment") "CC0402-X7R-4700 пФ-10%-50В"))
      (libsource (lib "Чип конденсаторы") (part "CC0402-X7R-#-20%-10В"))
    )
    (comp (ref "C229")
      (value "0,22 мкФ")
      (footprint "CC0402(1005)")
      (description "Чип конденсатор керамический")
      (fields (field (name "Comment") "CC0402-X7R-0,22 мкФ-10%-6.3В"))
      (libsource (lib "Чип конденсаторы") (part "CC0402-X7R-#-20%-10В"))
    )
    (comp (ref "C230")
      (value "0,22 мкФ")
      (footprint "CC0402(1005)")
      (description "Чип конденсатор керамический")
      (fields (field (name "Comment") "CC0402-X7R-0,22 мкФ-10%-6.3В"))
      (libsource (lib "Чип конденсаторы") (part "CC0402-X7R-#-20%-10В"))
    )
    (comp (ref "C231")
      (value "0,47 мкФ")
      (footprint "CC0402(1005)")
      (description "Чип конденсатор керамический")
      (fields (field (name "Comment") "CC0402-X7R-0,47 мкФ-10%-6.3В"))
      (libsource (lib "Чип конденсаторы") (part "CC0402-X7R-#-20%-10В"))
    )
    (comp (ref "C232")
      (value "0,1 мкФ")
      (footprint "CC0402(1005)")
      (description "Чип конденсатор керамический")
      (fields (field (name "Comment") "CC0402-X7R-0,1 мкФ-20%-10В"))
      (libsource (lib "Чип конденсаторы") (part "CC0402-X7R-#-20%-10В"))
    )
    (comp (ref "C233")
      (value "0,1 мкФ")
      (footprint "CC0402(1005)")
      (description "Чип конденсатор керамический")
      (fields (field (name "Comment") "CC0402-X7R-0,1 мкФ-20%-10В"))
      (libsource (lib "Чип конденсаторы") (part "CC0402-X7R-#-20%-10В"))
    )
    (comp (ref "C234")
      (value "0,01 мкФ")
      (footprint "CC0402(1005)")
      (description "Чип конденсатор керамический")
      (fields (field (name "Comment") "CC0402-X7R-0,01 мкФ-10%-50В"))
      (libsource (lib "Чип конденсаторы") (part "CC0402-X7R-#-20%-10В"))
    )
    (comp (ref "C235")
      (value "0,01 мкФ")
      (footprint "CC0402(1005)")
      (description "Чип конденсатор керамический")
      (fields (field (name "Comment") "CC0402-X7R-0,01 мкФ-10%-50В"))
      (libsource (lib "Чип конденсаторы") (part "CC0402-X7R-#-20%-10В"))
    )
    (comp (ref "C236")
      (value "0,01 мкФ")
      (footprint "CC0402(1005)")
      (description "Чип конденсатор керамический")
      (fields (field (name "Comment") "CC0402-X7R-0,01 мкФ-10%-50В"))
      (libsource (lib "Чип конденсаторы") (part "CC0402-X7R-#-20%-10В"))
    )
    (comp (ref "C237")
      (value "0,01 мкФ")
      (footprint "CC0402(1005)")
      (description "Чип конденсатор керамический")
      (fields (field (name "Comment") "CC0402-X7R-0,01 мкФ-10%-50В"))
      (libsource (lib "Чип конденсаторы") (part "CC0402-X7R-#-20%-10В"))
    )
    (comp (ref "C238")
      (value "0,01 мкФ")
      (footprint "CC0402(1005)")
      (description "Чип конденсатор керамический")
      (fields (field (name "Comment") "CC0402-X7R-0,01 мкФ-10%-50В"))
      (libsource (lib "Чип конденсаторы") (part "CC0402-X7R-#-20%-10В"))
    )
    (comp (ref "C239")
      (value "0,1 мкФ")
      (footprint "CC0402(1005)")
      (description "Чип конденсатор керамический")
      (fields (field (name "Comment") "CC0402-X7R-0,1 мкФ-20%-10В"))
      (libsource (lib "Чип конденсаторы") (part "CC0402-X7R-#-20%-10В"))
    )
    (comp (ref "C240")
      (value "0,1 мкФ")
      (footprint "CC0402(1005)")
      (description "Чип конденсатор керамический")
      (fields (field (name "Comment") "CC0402-X7R-0,1 мкФ-20%-10В"))
      (libsource (lib "Чип конденсаторы") (part "CC0402-X7R-#-20%-10В"))
    )
    (comp (ref "C241")
      (value "0,1 мкФ")
      (footprint "CC0402(1005)")
      (description "Чип конденсатор керамический")
      (fields (field (name "Comment") "CC0402-X7R-0,1 мкФ-20%-10В"))
      (libsource (lib "Чип конденсаторы") (part "CC0402-X7R-#-20%-10В"))
    )
    (comp (ref "C242")
      (value "0,1 мкФ")
      (footprint "CC0402(1005)")
      (description "Чип конденсатор керамический")
      (fields (field (name "Comment") "CC0402-X7R-0,1 мкФ-20%-10В"))
      (libsource (lib "Чип конденсаторы") (part "CC0402-X7R-#-20%-10В"))
    )
    (comp (ref "C243")
      (value "0,1 мкФ")
      (footprint "CC0402(1005)")
      (description "Чип конденсатор керамический")
      (fields (field (name "Comment") "CC0402-X7R-0,1 мкФ-20%-10В"))
      (libsource (lib "Чип конденсаторы") (part "CC0402-X7R-#-20%-10В"))
    )
    (comp (ref "C244")
      (value "0,01 мкФ")
      (footprint "CC0402(1005)")
      (description "Чип конденсатор керамический")
      (fields (field (name "Comment") "CC0402-X7R-0,01 мкФ-10%-50В"))
      (libsource (lib "Чип конденсаторы") (part "CC0402-X7R-#-20%-10В"))
    )
    (comp (ref "C245")
      (value "0,01 мкФ")
      (footprint "CC0402(1005)")
      (description "Чип конденсатор керамический")
      (fields (field (name "Comment") "CC0402-X7R-0,01 мкФ-10%-50В"))
      (libsource (lib "Чип конденсаторы") (part "CC0402-X7R-#-20%-10В"))
    )
    (comp (ref "C246")
      (value "4700 пФ")
      (footprint "CC0402(1005)")
      (description "Чип конденсатор керамический")
      (fields (field (name "Comment") "CC0402-X7R-4700 пФ-10%-50В"))
      (libsource (lib "Чип конденсаторы") (part "CC0402-X7R-#-20%-10В"))
    )
    (comp (ref "C247")
      (value "4700 пФ")
      (footprint "CC0402(1005)")
      (description "Чип конденсатор керамический")
      (fields (field (name "Comment") "CC0402-X7R-4700 пФ-10%-50В"))
      (libsource (lib "Чип конденсаторы") (part "CC0402-X7R-#-20%-10В"))
    )
    (comp (ref "C248")
      (value "0,22 мкФ")
      (footprint "CC0402(1005)")
      (description "Чип конденсатор керамический")
      (fields (field (name "Comment") "CC0402-X7R-0,22 мкФ-10%-6.3В"))
      (libsource (lib "Чип конденсаторы") (part "CC0402-X7R-#-20%-10В"))
    )
    (comp (ref "C249")
      (value "0,22 мкФ")
      (footprint "CC0402(1005)")
      (description "Чип конденсатор керамический")
      (fields (field (name "Comment") "CC0402-X7R-0,22 мкФ-10%-6.3В"))
      (libsource (lib "Чип конденсаторы") (part "CC0402-X7R-#-20%-10В"))
    )
    (comp (ref "C250")
      (value "0,47 мкФ")
      (footprint "CC0402(1005)")
      (description "Чип конденсатор керамический")
      (fields (field (name "Comment") "CC0402-X7R-0,47 мкФ-10%-6.3В"))
      (libsource (lib "Чип конденсаторы") (part "CC0402-X7R-#-20%-10В"))
    )
    (comp (ref "C251")
      (value "0,1 мкФ")
      (footprint "CC0402(1005)")
      (description "Чип конденсатор керамический")
      (fields (field (name "Comment") "CC0402-X7R-0,1 мкФ-20%-10В"))
      (libsource (lib "Чип конденсаторы") (part "CC0402-X7R-#-20%-10В"))
    )
    (comp (ref "C252")
      (value "0,1 мкФ")
      (footprint "CC0402(1005)")
      (description "Чип конденсатор керамический")
      (fields (field (name "Comment") "CC0402-X7R-0,1 мкФ-20%-10В"))
      (libsource (lib "Чип конденсаторы") (part "CC0402-X7R-#-20%-10В"))
    )
    (comp (ref "C253")
      (value "0,1 мкФ")
      (footprint "CC0402(1005)")
      (description "Чип конденсатор керамический")
      (fields (field (name "Comment") "CC0402-X7R-0,1 мкФ-20%-10В"))
      (libsource (lib "Чип конденсаторы") (part "CC0402-X7R-#-20%-10В"))
    )
    (comp (ref "C254")
      (value "0,22 мкФ")
      (footprint "CC0402(1005)")
      (description "Чип конденсатор керамический")
      (fields (field (name "Comment") "CC0402-X7R-0,22 мкФ-10%-6.3В"))
      (libsource (lib "Чип конденсаторы") (part "CC0402-X7R-#-20%-10В"))
    )
    (comp (ref "C255")
      (value "0,01 мкФ")
      (footprint "CC0402(1005)")
      (description "Чип конденсатор керамический")
      (fields (field (name "Comment") "CC0402-X7R-0,01 мкФ-10%-50В"))
      (libsource (lib "Чип конденсаторы") (part "CC0402-X7R-#-20%-10В"))
    )
    (comp (ref "C256")
      (value "0,01 мкФ")
      (footprint "CC0402(1005)")
      (description "Чип конденсатор керамический")
      (fields (field (name "Comment") "CC0402-X7R-0,01 мкФ-10%-50В"))
      (libsource (lib "Чип конденсаторы") (part "CC0402-X7R-#-20%-10В"))
    )
    (comp (ref "C257")
      (value "0,01 мкФ")
      (footprint "CC0402(1005)")
      (description "Чип конденсатор керамический")
      (fields (field (name "Comment") "CC0402-X7R-0,01 мкФ-10%-50В"))
      (libsource (lib "Чип конденсаторы") (part "CC0402-X7R-#-20%-10В"))
    )
    (comp (ref "C258")
      (value "0,01 мкФ")
      (footprint "CC0402(1005)")
      (description "Чип конденсатор керамический")
      (fields (field (name "Comment") "CC0402-X7R-0,01 мкФ-10%-50В"))
      (libsource (lib "Чип конденсаторы") (part "CC0402-X7R-#-20%-10В"))
    )
    (comp (ref "C259")
      (value "0,1 мкФ")
      (footprint "CC0402(1005)")
      (description "Чип конденсатор керамический")
      (fields (field (name "Comment") "CC0402-X7R-0,1 мкФ-20%-10В"))
      (libsource (lib "Чип конденсаторы") (part "CC0402-X7R-#-20%-10В"))
    )
    (comp (ref "C260")
      (value "0,1 мкФ")
      (footprint "CC0402(1005)")
      (description "Чип конденсатор керамический")
      (fields (field (name "Comment") "CC0402-X7R-0,1 мкФ-20%-10В"))
      (libsource (lib "Чип конденсаторы") (part "CC0402-X7R-#-20%-10В"))
    )
    (comp (ref "C261")
      (value "0,1 мкФ")
      (footprint "CC0402(1005)")
      (description "Чип конденсатор керамический")
      (fields (field (name "Comment") "CC0402-X7R-0,1 мкФ-20%-10В"))
      (libsource (lib "Чип конденсаторы") (part "CC0402-X7R-#-20%-10В"))
    )
    (comp (ref "C262")
      (value "0,22 мкФ")
      (footprint "CC0402(1005)")
      (description "Чип конденсатор керамический")
      (fields (field (name "Comment") "CC0402-X7R-0,22 мкФ-10%-6.3В"))
      (libsource (lib "Чип конденсаторы") (part "CC0402-X7R-#-20%-10В"))
    )
    (comp (ref "C263")
      (value "0,01 мкФ")
      (footprint "CC0402(1005)")
      (description "Чип конденсатор керамический")
      (fields (field (name "Comment") "CC0402-X7R-0,01 мкФ-10%-50В"))
      (libsource (lib "Чип конденсаторы") (part "CC0402-X7R-#-20%-10В"))
    )
    (comp (ref "C264")
      (value "0,01 мкФ")
      (footprint "CC0402(1005)")
      (description "Чип конденсатор керамический")
      (fields (field (name "Comment") "CC0402-X7R-0,01 мкФ-10%-50В"))
      (libsource (lib "Чип конденсаторы") (part "CC0402-X7R-#-20%-10В"))
    )
    (comp (ref "C265")
      (value "0,01 мкФ")
      (footprint "CC0402(1005)")
      (description "Чип конденсатор керамический")
      (fields (field (name "Comment") "CC0402-X7R-0,01 мкФ-10%-50В"))
      (libsource (lib "Чип конденсаторы") (part "CC0402-X7R-#-20%-10В"))
    )
    (comp (ref "C266")
      (value "0,01 мкФ")
      (footprint "CC0402(1005)")
      (description "Чип конденсатор керамический")
      (fields (field (name "Comment") "CC0402-X7R-0,01 мкФ-10%-50В"))
      (libsource (lib "Чип конденсаторы") (part "CC0402-X7R-#-20%-10В"))
    )
    (comp (ref "D2")
      (value "5CSXFC6D6F31I7N")
      (footprint "ALTR-FBGA896_A-200")
      (fields (field (name "MANUFACTURER") "Altera"))
      (libsource (lib "Altera Cyclone V_sd") (part "5CSXFC6D6F31I7N"))
    )
    (comp (ref "L1")
      (value "MH1608-600Y")
      (footprint "CL0805")
      (description "Чип индуктивность подавления EMP")
      (libsource (lib "Индуктивности") (part "BLM21"))
    )
    (comp (ref "L2")
      (value "MH1608-600Y")
      (footprint "CL0805")
      (description "Чип индуктивность подавления EMP")
      (libsource (lib "Индуктивности") (part "BLM21"))
    )
    (comp (ref "L3")
      (value "BLM18PG-60 Ом")
      (footprint "CL0603")
      (description "Чип индуктивность подавления EMP")
      (libsource (lib "Индуктивности") (part "BLM18"))
    )
    (comp (ref "L4")
      (value "BLM18PG-60 Ом")
      (footprint "CL0603")
      (description "Чип индуктивность подавления EMP")
      (libsource (lib "Индуктивности") (part "BLM18"))
    )
    (comp (ref "L5")
      (value "BLM18PG-60 Ом")
      (footprint "CL0603")
      (description "Чип индуктивность подавления EMP")
      (libsource (lib "Индуктивности") (part "BLM18"))
    )
    (comp (ref "L6")
      (value "BLM18PG-60 Ом")
      (footprint "CL0603")
      (description "Чип индуктивность подавления EMP")
      (libsource (lib "Индуктивности") (part "BLM18"))
    )
    (comp (ref "L13")
      (value "BLM18PG-60 Ом")
      (footprint "CL0603")
      (description "Чип индуктивность подавления EMP")
      (libsource (lib "Индуктивности") (part "BLM18"))
    )
  )
  (nets
    (net (code "1") (name "DDR3_VREF_FPGA") (class "Default")
      (node (ref "C167") (pin "1") (pinfunction "+_1") (pintype "passive"))
      (node (ref "D2") (pin "AJ15") (pinfunction "VREFB3BN0_AJ15") (pintype "power_in"))
      (node (ref "D2") (pin "AK17") (pinfunction "VREFB4AN0_AK17") (pintype "power_in"))
    )
    (net (code "2") (name "DDR3_VREF_HPS") (class "Default")
      (node (ref "D2") (pin "G27") (pinfunction "VREFB6AN0_HPS_G27") (pintype "power_in"))
      (node (ref "D2") (pin "U30") (pinfunction "VREFB6BN0_HPS_U30") (pintype "power_in"))
    )
    (net (code "3") (name "GND") (class "Default")
      (node (ref "C103") (pin "1") (pinfunction "+_1") (pintype "passive"))
      (node (ref "C105") (pin "1") (pinfunction "+_1") (pintype "passive"))
      (node (ref "C106") (pin "1") (pinfunction "+_1") (pintype "passive"))
      (node (ref "C107") (pin "1") (pinfunction "+_1") (pintype "passive"))
      (node (ref "C108") (pin "1") (pinfunction "+_1") (pintype "passive"))
      (node (ref "C109") (pin "1") (pinfunction "+_1") (pintype "passive"))
      (node (ref "C110") (pin "1") (pinfunction "+_1") (pintype "passive"))
      (node (ref "C111") (pin "1") (pinfunction "+_1") (pintype "passive"))
      (node (ref "C112") (pin "2") (pinfunction "-_2") (pintype "passive"))
      (node (ref "C113") (pin "1") (pinfunction "+_1") (pintype "passive"))
      (node (ref "C114") (pin "1") (pinfunction "+_1") (pintype "passive"))
      (node (ref "C115") (pin "1") (pinfunction "+_1") (pintype "passive"))
      (node (ref "C116") (pin "1") (pinfunction "+_1") (pintype "passive"))
      (node (ref "C117") (pin "1") (pinfunction "+_1") (pintype "passive"))
      (node (ref "C118") (pin "1") (pinfunction "+_1") (pintype "passive"))
      (node (ref "C119") (pin "1") (pinfunction "+_1") (pintype "passive"))
      (node (ref "C120") (pin "1") (pinfunction "+_1") (pintype "passive"))
      (node (ref "C121") (pin "1") (pinfunction "+_1") (pintype "passive"))
      (node (ref "C122") (pin "1") (pinfunction "+_1") (pintype "passive"))
      (node (ref "C123") (pin "1") (pinfunction "+_1") (pintype "passive"))
      (node (ref "C124") (pin "1") (pinfunction "+_1") (pintype "passive"))
      (node (ref "C125") (pin "1") (pinfunction "+_1") (pintype "passive"))
      (node (ref "C126") (pin "1") (pinfunction "+_1") (pintype "passive"))
      (node (ref "C127") (pin "1") (pinfunction "+_1") (pintype "passive"))
      (node (ref "C128") (pin "1") (pinfunction "+_1") (pintype "passive"))
      (node (ref "C129") (pin "1") (pinfunction "+_1") (pintype "passive"))
      (node (ref "C130") (pin "1") (pinfunction "+_1") (pintype "passive"))
      (node (ref "C131") (pin "1") (pinfunction "+_1") (pintype "passive"))
      (node (ref "C132") (pin "1") (pinfunction "+_1") (pintype "passive"))
      (node (ref "C133") (pin "1") (pinfunction "+_1") (pintype "passive"))
      (node (ref "C134") (pin "1") (pinfunction "+_1") (pintype "passive"))
      (node (ref "C135") (pin "1") (pinfunction "+_1") (pintype "passive"))
      (node (ref "C136") (pin "1") (pinfunction "+_1") (pintype "passive"))
      (node (ref "C137") (pin "2") (pinfunction "-_2") (pintype "passive"))
      (node (ref "C138") (pin "1") (pinfunction "+_1") (pintype "passive"))
      (node (ref "C139") (pin "1") (pinfunction "+_1") (pintype "passive"))
      (node (ref "C140") (pin "1") (pinfunction "+_1") (pintype "passive"))
      (node (ref "C141") (pin "1") (pinfunction "+_1") (pintype "passive"))
      (node (ref "C142") (pin "1") (pinfunction "+_1") (pintype "passive"))
      (node (ref "C143") (pin "1") (pinfunction "+_1") (pintype "passive"))
      (node (ref "C144") (pin "1") (pinfunction "+_1") (pintype "passive"))
      (node (ref "C145") (pin "1") (pinfunction "+_1") (pintype "passive"))
      (node (ref "C146") (pin "1") (pinfunction "+_1") (pintype "passive"))
      (node (ref "C147") (pin "1") (pinfunction "+_1") (pintype "passive"))
      (node (ref "C148") (pin "1") (pinfunction "+_1") (pintype "passive"))
      (node (ref "C149") (pin "1") (pinfunction "+_1") (pintype "passive"))
      (node (ref "C150") (pin "1") (pinfunction "+_1") (pintype "passive"))
      (node (ref "C151") (pin "1") (pinfunction "+_1") (pintype "passive"))
      (node (ref "C152") (pin "1") (pinfunction "+_1") (pintype "passive"))
      (node (ref "C153") (pin "1") (pinfunction "+_1") (pintype "passive"))
      (node (ref "C154") (pin "2") (pinfunction "-_2") (pintype "passive"))
      (node (ref "C155") (pin "1") (pinfunction "+_1") (pintype "passive"))
      (node (ref "C156") (pin "1") (pinfunction "+_1") (pintype "passive"))
      (node (ref "C157") (pin "1") (pinfunction "+_1") (pintype "passive"))
      (node (ref "C158") (pin "1") (pinfunction "+_1") (pintype "passive"))
      (node (ref "C159") (pin "1") (pinfunction "+_1") (pintype "passive"))
      (node (ref "C160") (pin "1") (pinfunction "+_1") (pintype "passive"))
      (node (ref "C161") (pin "1") (pinfunction "+_1") (pintype "passive"))
      (node (ref "C162") (pin "2") (pinfunction "-_2") (pintype "passive"))
      (node (ref "C163") (pin "2") (pinfunction "-_2") (pintype "passive"))
      (node (ref "C164") (pin "1") (pinfunction "+_1") (pintype "passive"))
      (node (ref "C165") (pin "1") (pinfunction "+_1") (pintype "passive"))
      (node (ref "C166") (pin "1") (pinfunction "+_1") (pintype "passive"))
      (node (ref "C167") (pin "2") (pinfunction "-_2") (pintype "passive"))
      (node (ref "C168") (pin "2") (pinfunction "-_2") (pintype "passive"))
      (node (ref "C169") (pin "2") (pinfunction "-_2") (pintype "passive"))
      (node (ref "C170") (pin "2") (pinfunction "-_2") (pintype "passive"))
      (node (ref "C171") (pin "2") (pinfunction "-_2") (pintype "passive"))
      (node (ref "C172") (pin "2") (pinfunction "-_2") (pintype "passive"))
      (node (ref "C173") (pin "2") (pinfunction "-_2") (pintype "passive"))
      (node (ref "C174") (pin "2") (pinfunction "-_2") (pintype "passive"))
      (node (ref "C175") (pin "2") (pinfunction "-_2") (pintype "passive"))
      (node (ref "C176") (pin "1") (pinfunction "+_1") (pintype "passive"))
      (node (ref "C177") (pin "1") (pinfunction "+_1") (pintype "passive"))
      (node (ref "C178") (pin "1") (pinfunction "+_1") (pintype "passive"))
      (node (ref "C179") (pin "1") (pinfunction "+_1") (pintype "passive"))
      (node (ref "C180") (pin "2") (pinfunction "-_2") (pintype "passive"))
      (node (ref "C181") (pin "2") (pinfunction "-_2") (pintype "passive"))
      (node (ref "C182") (pin "2") (pinfunction "-_2") (pintype "passive"))
      (node (ref "C183") (pin "2") (pinfunction "-_2") (pintype "passive"))
      (node (ref "C184") (pin "2") (pinfunction "-_2") (pintype "passive"))
      (node (ref "C185") (pin "2") (pinfunction "-_2") (pintype "passive"))
      (node (ref "C186") (pin "2") (pinfunction "-_2") (pintype "passive"))
      (node (ref "C187") (pin "2") (pinfunction "-_2") (pintype "passive"))
      (node (ref "C188") (pin "2") (pinfunction "-_2") (pintype "passive"))
      (node (ref "C189") (pin "2") (pinfunction "-_2") (pintype "passive"))
      (node (ref "C190") (pin "2") (pinfunction "-_2") (pintype "passive"))
      (node (ref "C191") (pin "2") (pinfunction "-_2") (pintype "passive"))
      (node (ref "C192") (pin "2") (pinfunction "-_2") (pintype "passive"))
      (node (ref "C193") (pin "2") (pinfunction "-_2") (pintype "passive"))
      (node (ref "C194") (pin "1") (pinfunction "+_1") (pintype "passive"))
      (node (ref "C195") (pin "1") (pinfunction "+_1") (pintype "passive"))
      (node (ref "C196") (pin "1") (pinfunction "+_1") (pintype "passive"))
      (node (ref "C197") (pin "1") (pinfunction "+_1") (pintype "passive"))
      (node (ref "C198") (pin "1") (pinfunction "+_1") (pintype "passive"))
      (node (ref "C199") (pin "1") (pinfunction "+_1") (pintype "passive"))
      (node (ref "C200") (pin "1") (pinfunction "+_1") (pintype "passive"))
      (node (ref "C201") (pin "1") (pinfunction "+_1") (pintype "passive"))
      (node (ref "C202") (pin "2") (pinfunction "-_2") (pintype "passive"))
      (node (ref "C203") (pin "2") (pinfunction "-_2") (pintype "passive"))
      (node (ref "C204") (pin "2") (pinfunction "-_2") (pintype "passive"))
      (node (ref "C205") (pin "2") (pinfunction "-_2") (pintype "passive"))
      (node (ref "C206") (pin "1") (pinfunction "+_1") (pintype "passive"))
      (node (ref "C207") (pin "1") (pinfunction "+_1") (pintype "passive"))
      (node (ref "C208") (pin "1") (pinfunction "+_1") (pintype "passive"))
      (node (ref "C209") (pin "1") (pinfunction "+_1") (pintype "passive"))
      (node (ref "C210") (pin "1") (pinfunction "+_1") (pintype "passive"))
      (node (ref "C211") (pin "1") (pinfunction "+_1") (pintype "passive"))
      (node (ref "C212") (pin "1") (pinfunction "+_1") (pintype "passive"))
      (node (ref "C213") (pin "1") (pinfunction "+_1") (pintype "passive"))
      (node (ref "C214") (pin "1") (pinfunction "+_1") (pintype "passive"))
      (node (ref "C215") (pin "1") (pinfunction "+_1") (pintype "passive"))
      (node (ref "C216") (pin "1") (pinfunction "+_1") (pintype "passive"))
      (node (ref "C217") (pin "1") (pinfunction "+_1") (pintype "passive"))
      (node (ref "C218") (pin "1") (pinfunction "+_1") (pintype "passive"))
      (node (ref "C219") (pin "1") (pinfunction "+_1") (pintype "passive"))
      (node (ref "C220") (pin "1") (pinfunction "+_1") (pintype "passive"))
      (node (ref "C221") (pin "1") (pinfunction "+_1") (pintype "passive"))
      (node (ref "C222") (pin "1") (pinfunction "+_1") (pintype "passive"))
      (node (ref "C223") (pin "1") (pinfunction "+_1") (pintype "passive"))
      (node (ref "C224") (pin "1") (pinfunction "+_1") (pintype "passive"))
      (node (ref "C225") (pin "1") (pinfunction "+_1") (pintype "passive"))
      (node (ref "C226") (pin "1") (pinfunction "+_1") (pintype "passive"))
      (node (ref "C227") (pin "2") (pinfunction "-_2") (pintype "passive"))
      (node (ref "C228") (pin "2") (pinfunction "-_2") (pintype "passive"))
      (node (ref "C230") (pin "1") (pinfunction "+_1") (pintype "passive"))
      (node (ref "C231") (pin "1") (pinfunction "+_1") (pintype "passive"))
      (node (ref "C232") (pin "1") (pinfunction "+_1") (pintype "passive"))
      (node (ref "C233") (pin "1") (pinfunction "+_1") (pintype "passive"))
      (node (ref "C234") (pin "1") (pinfunction "+_1") (pintype "passive"))
      (node (ref "C235") (pin "1") (pinfunction "+_1") (pintype "passive"))
      (node (ref "C236") (pin "1") (pinfunction "+_1") (pintype "passive"))
      (node (ref "C237") (pin "1") (pinfunction "+_1") (pintype "passive"))
      (node (ref "C238") (pin "1") (pinfunction "+_1") (pintype "passive"))
      (node (ref "C239") (pin "1") (pinfunction "+_1") (pintype "passive"))
      (node (ref "C240") (pin "1") (pinfunction "+_1") (pintype "passive"))
      (node (ref "C241") (pin "1") (pinfunction "+_1") (pintype "passive"))
      (node (ref "C242") (pin "1") (pinfunction "+_1") (pintype "passive"))
      (node (ref "C243") (pin "1") (pinfunction "+_1") (pintype "passive"))
      (node (ref "C244") (pin "1") (pinfunction "+_1") (pintype "passive"))
      (node (ref "C245") (pin "1") (pinfunction "+_1") (pintype "passive"))
      (node (ref "C246") (pin "2") (pinfunction "-_2") (pintype "passive"))
      (node (ref "C247") (pin "2") (pinfunction "-_2") (pintype "passive"))
      (node (ref "C249") (pin "1") (pinfunction "+_1") (pintype "passive"))
      (node (ref "C250") (pin "1") (pinfunction "+_1") (pintype "passive"))
      (node (ref "C251") (pin "1") (pinfunction "+_1") (pintype "passive"))
      (node (ref "C252") (pin "1") (pinfunction "+_1") (pintype "passive"))
      (node (ref "C253") (pin "1") (pinfunction "+_1") (pintype "passive"))
      (node (ref "C254") (pin "1") (pinfunction "+_1") (pintype "passive"))
      (node (ref "C255") (pin "1") (pinfunction "+_1") (pintype "passive"))
      (node (ref "C256") (pin "1") (pinfunction "+_1") (pintype "passive"))
      (node (ref "C257") (pin "1") (pinfunction "+_1") (pintype "passive"))
      (node (ref "C258") (pin "1") (pinfunction "+_1") (pintype "passive"))
      (node (ref "C259") (pin "1") (pinfunction "+_1") (pintype "passive"))
      (node (ref "C260") (pin "1") (pinfunction "+_1") (pintype "passive"))
      (node (ref "C261") (pin "1") (pinfunction "+_1") (pintype "passive"))
      (node (ref "C262") (pin "1") (pinfunction "+_1") (pintype "passive"))
      (node (ref "C263") (pin "1") (pinfunction "+_1") (pintype "passive"))
      (node (ref "C264") (pin "1") (pinfunction "+_1") (pintype "passive"))
      (node (ref "C265") (pin "1") (pinfunction "+_1") (pintype "passive"))
      (node (ref "C266") (pin "1") (pinfunction "+_1") (pintype "passive"))
      (node (ref "C70") (pin "1") (pinfunction "+_1") (pintype "passive"))
      (node (ref "C87") (pin "2") (pinfunction "-_2") (pintype "passive"))
      (node (ref "C94") (pin "2") (pinfunction "-_2") (pintype "passive"))
      (node (ref "D2") (pin "A12") (pinfunction "GND_A12") (pintype "power_in"))
      (node (ref "D2") (pin "A17") (pinfunction "GND_A17") (pintype "power_in"))
      (node (ref "D2") (pin "A2") (pinfunction "GND_A2") (pintype "power_in"))
      (node (ref "D2") (pin "A22") (pinfunction "GND_A22") (pintype "power_in"))
      (node (ref "D2") (pin "A26") (pinfunction "GND_A26") (pintype "power_in"))
      (node (ref "D2") (pin "A27") (pinfunction "GND_A27") (pintype "power_in"))
      (node (ref "D2") (pin "AA11") (pinfunction "GND_AA11") (pintype "power_in"))
      (node (ref "D2") (pin "AA22") (pinfunction "GND_AA22") (pintype "power_in"))
      (node (ref "D2") (pin "AA29") (pinfunction "VREFB5BN0_AA29") (pintype "power_in"))
      (node (ref "D2") (pin "AA3") (pinfunction "GND_AA3") (pintype "power_in"))
      (node (ref "D2") (pin "AA4") (pinfunction "GND_AA4") (pintype "power_in"))
      (node (ref "D2") (pin "AA6") (pinfunction "GND_AA6") (pintype "power_in"))
      (node (ref "D2") (pin "AA9") (pinfunction "GND_AA9") (pintype "power_in"))
      (node (ref "D2") (pin "AB1") (pinfunction "GND_AB1") (pintype "power_in"))
      (node (ref "D2") (pin "AB19") (pinfunction "GND_AB19") (pintype "power_in"))
      (node (ref "D2") (pin "AB2") (pinfunction "GND_AB2") (pintype "power_in"))
      (node (ref "D2") (pin "AB29") (pinfunction "GND_AB29") (pintype "power_in"))
      (node (ref "D2") (pin "AB5") (pinfunction "GND_AB5") (pintype "power_in"))
      (node (ref "D2") (pin "AB7") (pinfunction "GND_AB7") (pintype "power_in"))
      (node (ref "D2") (pin "AC16") (pinfunction "GND_AC16") (pintype "power_in"))
      (node (ref "D2") (pin "AC24") (pinfunction "VREFB5AN0_AC24") (pintype "power_in"))
      (node (ref "D2") (pin "AC26") (pinfunction "GND_AC26") (pintype "power_in"))
      (node (ref "D2") (pin "AC3") (pinfunction "GND_AC3") (pintype "power_in"))
      (node (ref "D2") (pin "AC4") (pinfunction "GND_AC4") (pintype "power_in"))
      (node (ref "D2") (pin "AC6") (pinfunction "GND_AC6") (pintype "power_in"))
      (node (ref "D2") (pin "AC8") (pinfunction "GND_AC8") (pintype "power_in"))
      (node (ref "D2") (pin "AD1") (pinfunction "GND_AD1") (pintype "power_in"))
      (node (ref "D2") (pin "AD2") (pinfunction "GND_AD2") (pintype "power_in"))
      (node (ref "D2") (pin "AD23") (pinfunction "GND_AD23") (pintype "power_in"))
      (node (ref "D2") (pin "AD5") (pinfunction "GND_AD5") (pintype "power_in"))
      (node (ref "D2") (pin "AD6") (pinfunction "VREFB3AN0_AD6") (pintype "power_in"))
      (node (ref "D2") (pin "AE10") (pinfunction "GND_AE10") (pintype "power_in"))
      (node (ref "D2") (pin "AE20") (pinfunction "GND_AE20") (pintype "power_in"))
      (node (ref "D2") (pin "AE3") (pinfunction "GND_AE3") (pintype "power_in"))
      (node (ref "D2") (pin "AE4") (pinfunction "GND_AE4") (pintype "power_in"))
      (node (ref "D2") (pin "AF1") (pinfunction "GND_AF1") (pintype "power_in"))
      (node (ref "D2") (pin "AF12") (pinfunction "GND_AF12") (pintype "power_in"))
      (node (ref "D2") (pin "AF17") (pinfunction "GND_AF17") (pintype "power_in"))
      (node (ref "D2") (pin "AF2") (pinfunction "GND_AF2") (pintype "power_in"))
      (node (ref "D2") (pin "AF27") (pinfunction "GND_AF27") (pintype "power_in"))
      (node (ref "D2") (pin "AF3") (pinfunction "GND_AF3") (pintype "power_in"))
      (node (ref "D2") (pin "AG14") (pinfunction "GND_AG14") (pintype "power_in"))
      (node (ref "D2") (pin "AG24") (pinfunction "GND_AG24") (pintype "power_in"))
      (node (ref "D2") (pin "AG9") (pinfunction "GND_AG9") (pintype "power_in"))
      (node (ref "D2") (pin "AH1") (pinfunction "GND_AH1") (pintype "power_in"))
      (node (ref "D2") (pin "AH11") (pinfunction "GND_AH11") (pintype "power_in"))
      (node (ref "D2") (pin "AH21") (pinfunction "GND_AH21") (pintype "power_in"))
      (node (ref "D2") (pin "AH6") (pinfunction "GND_AH6") (pintype "power_in"))
      (node (ref "D2") (pin "AJ18") (pinfunction "GND_AJ18") (pintype "power_in"))
      (node (ref "D2") (pin "AJ28") (pinfunction "GND_AJ28") (pintype "power_in"))
      (node (ref "D2") (pin "AJ3") (pinfunction "GND_AJ3") (pintype "power_in"))
      (node (ref "D2") (pin "AJ30") (pinfunction "GND_AJ30") (pintype "power_in"))
      (node (ref "D2") (pin "AK15") (pinfunction "GND_AK15") (pintype "power_in"))
      (node (ref "D2") (pin "AK25") (pinfunction "GND_AK25") (pintype "power_in"))
      (node (ref "D2") (pin "AK5") (pinfunction "GND_AK5") (pintype "power_in"))
      (node (ref "D2") (pin "B10") (pinfunction "VREFB8AN0_B10") (pintype "power_in"))
      (node (ref "D2") (pin "B14") (pinfunction "GND_B14") (pintype "power_in"))
      (node (ref "D2") (pin "B19") (pinfunction "GND_B19") (pintype "power_in"))
      (node (ref "D2") (pin "B24") (pinfunction "GND_B24") (pintype "power_in"))
      (node (ref "D2") (pin "B29") (pinfunction "GND_B29") (pintype "power_in"))
      (node (ref "D2") (pin "B9") (pinfunction "GND_B9") (pintype "power_in"))
      (node (ref "D2") (pin "C1") (pinfunction "GND_C1") (pintype "power_in"))
      (node (ref "D2") (pin "C16") (pinfunction "GND_C16") (pintype "power_in"))
      (node (ref "D2") (pin "C21") (pinfunction "GND_C21") (pintype "power_in"))
      (node (ref "D2") (pin "C26") (pinfunction "GND_C26") (pintype "power_in"))
      (node (ref "D2") (pin "C6") (pinfunction "GND_C6") (pintype "power_in"))
      (node (ref "D2") (pin "D13") (pinfunction "GND_D13") (pintype "power_in"))
      (node (ref "D2") (pin "D23") (pinfunction "GND_D23") (pintype "power_in"))
      (node (ref "D2") (pin "D26") (pinfunction "GND_D26") (pintype "power_in"))
      (node (ref "D2") (pin "D3") (pinfunction "GND_D3") (pintype "power_in"))
      (node (ref "D2") (pin "E10") (pinfunction "GND_E10") (pintype "power_in"))
      (node (ref "D2") (pin "E22") (pinfunction "VREFB7A7B7C7DN0_HPS_E22") (pintype "power_in"))
      (node (ref "D2") (pin "E25") (pinfunction "GND_E25") (pintype "power_in"))
      (node (ref "D2") (pin "E30") (pinfunction "GND_E30") (pintype "power_in"))
      (node (ref "D2") (pin "F17") (pinfunction "GND_F17") (pintype "power_in"))
      (node (ref "D2") (pin "F2") (pinfunction "GND_F2") (pintype "power_in"))
      (node (ref "D2") (pin "F27") (pinfunction "GND_F27") (pintype "power_in"))
      (node (ref "D2") (pin "F5") (pinfunction "GND_F5") (pintype "power_in"))
      (node (ref "D2") (pin "F7") (pinfunction "GND_F7") (pintype "power_in"))
      (node (ref "D2") (pin "G24") (pinfunction "GND_G24") (pintype "power_in"))
      (node (ref "D2") (pin "G3") (pinfunction "GND_G3") (pintype "power_in"))
      (node (ref "D2") (pin "G4") (pinfunction "GND_G4") (pintype "power_in"))
      (node (ref "D2") (pin "H1") (pinfunction "GND_H1") (pintype "power_in"))
      (node (ref "D2") (pin "H11") (pinfunction "GND_H11") (pintype "power_in"))
      (node (ref "D2") (pin "H2") (pinfunction "GND_H2") (pintype "power_in"))
      (node (ref "D2") (pin "H5") (pinfunction "GND_H5") (pintype "power_in"))
      (node (ref "D2") (pin "J18") (pinfunction "GND_J18") (pintype "power_in"))
      (node (ref "D2") (pin "J22") (pinfunction "GND_J22") (pintype "power_in"))
      (node (ref "D2") (pin "J28") (pinfunction "GND_J28") (pintype "power_in"))
      (node (ref "D2") (pin "J3") (pinfunction "GND_J3") (pintype "power_in"))
      (node (ref "D2") (pin "J4") (pinfunction "GND_J4") (pintype "power_in"))
      (node (ref "D2") (pin "J6") (pinfunction "GND_J6") (pintype "power_in"))
      (node (ref "D2") (pin "J8") (pinfunction "GND_J8") (pintype "power_in"))
      (node (ref "D2") (pin "K1") (pinfunction "GND_K1") (pintype "power_in"))
      (node (ref "D2") (pin "K10") (pinfunction "GND_K10") (pintype "power_in"))
      (node (ref "D2") (pin "K15") (pinfunction "GND_K15") (pintype "power_in"))
      (node (ref "D2") (pin "K2") (pinfunction "GND_K2") (pintype "power_in"))
      (node (ref "D2") (pin "K20") (pinfunction "GND_K20") (pintype "power_in"))
      (node (ref "D2") (pin "K25") (pinfunction "GND_K25") (pintype "power_in"))
      (node (ref "D2") (pin "K5") (pinfunction "GND_K5") (pintype "power_in"))
      (node (ref "D2") (pin "L11") (pinfunction "GND_L11") (pintype "power_in"))
      (node (ref "D2") (pin "L13") (pinfunction "GND_L13") (pintype "power_in"))
      (node (ref "D2") (pin "L15") (pinfunction "GND_L15") (pintype "power_in"))
      (node (ref "D2") (pin "L17") (pinfunction "GND_L17") (pintype "power_in"))
      (node (ref "D2") (pin "L19") (pinfunction "GND_L19") (pintype "power_in"))
      (node (ref "D2") (pin "L22") (pinfunction "GND_L22") (pintype "power_in"))
      (node (ref "D2") (pin "L3") (pinfunction "GND_L3") (pintype "power_in"))
      (node (ref "D2") (pin "L4") (pinfunction "GND_L4") (pintype "power_in"))
      (node (ref "D2") (pin "L6") (pinfunction "GND_L6") (pintype "power_in"))
      (node (ref "D2") (pin "M1") (pinfunction "GND_M1") (pintype "power_in"))
      (node (ref "D2") (pin "M10") (pinfunction "GND_M10") (pintype "power_in"))
      (node (ref "D2") (pin "M12") (pinfunction "GND_M12") (pintype "power_in"))
      (node (ref "D2") (pin "M14") (pinfunction "GND_M14") (pintype "power_in"))
      (node (ref "D2") (pin "M16") (pinfunction "GND_M16") (pintype "power_in"))
      (node (ref "D2") (pin "M18") (pinfunction "GND_M18") (pintype "power_in"))
      (node (ref "D2") (pin "M2") (pinfunction "GND_M2") (pintype "power_in"))
      (node (ref "D2") (pin "M20") (pinfunction "GND_M20") (pintype "power_in"))
      (node (ref "D2") (pin "M29") (pinfunction "GND_M29") (pintype "power_in"))
      (node (ref "D2") (pin "M5") (pinfunction "GND_M5") (pintype "power_in"))
      (node (ref "D2") (pin "M7") (pinfunction "GND_M7") (pintype "power_in"))
      (node (ref "D2") (pin "M8") (pinfunction "GND_M8") (pintype "power_in"))
      (node (ref "D2") (pin "N11") (pinfunction "GND_N11") (pintype "power_in"))
      (node (ref "D2") (pin "N13") (pinfunction "GND_N13") (pintype "power_in"))
      (node (ref "D2") (pin "N15") (pinfunction "GND_N15") (pintype "power_in"))
      (node (ref "D2") (pin "N17") (pinfunction "GND_N17") (pintype "power_in"))
      (node (ref "D2") (pin "N19") (pinfunction "GND_N19") (pintype "power_in"))
      (node (ref "D2") (pin "N26") (pinfunction "GND_N26") (pintype "power_in"))
      (node (ref "D2") (pin "N3") (pinfunction "GND_N3") (pintype "power_in"))
      (node (ref "D2") (pin "N4") (pinfunction "GND_N4") (pintype "power_in"))
      (node (ref "D2") (pin "N6") (pinfunction "GND_N6") (pintype "power_in"))
      (node (ref "D2") (pin "N8") (pinfunction "GND_N8") (pintype "power_in"))
      (node (ref "D2") (pin "N9") (pinfunction "GND_N9") (pintype "power_in"))
      (node (ref "D2") (pin "P1") (pinfunction "GND_P1") (pintype "power_in"))
      (node (ref "D2") (pin "P10") (pinfunction "GND_P10") (pintype "power_in"))
      (node (ref "D2") (pin "P12") (pinfunction "GND_P12") (pintype "power_in"))
      (node (ref "D2") (pin "P14") (pinfunction "GND_P14") (pintype "power_in"))
      (node (ref "D2") (pin "P16") (pinfunction "GND_P16") (pintype "power_in"))
      (node (ref "D2") (pin "P18") (pinfunction "GND_P18") (pintype "power_in"))
      (node (ref "D2") (pin "P2") (pinfunction "GND_P2") (pintype "power_in"))
      (node (ref "D2") (pin "P20") (pinfunction "GND_P20") (pintype "power_in"))
      (node (ref "D2") (pin "P5") (pinfunction "GND_P5") (pintype "power_in"))
      (node (ref "D2") (pin "P7") (pinfunction "GND_P7") (pintype "power_in"))
      (node (ref "D2") (pin "R11") (pinfunction "GND_R11") (pintype "power_in"))
      (node (ref "D2") (pin "R13") (pinfunction "GND_R13") (pintype "power_in"))
      (node (ref "D2") (pin "R15") (pinfunction "GND_R15") (pintype "power_in"))
      (node (ref "D2") (pin "R17") (pinfunction "GND_R17") (pintype "power_in"))
      (node (ref "D2") (pin "R3") (pinfunction "GND_R3") (pintype "power_in"))
      (node (ref "D2") (pin "R30") (pinfunction "GND_R30") (pintype "power_in"))
      (node (ref "D2") (pin "R4") (pinfunction "GND_R4") (pintype "power_in"))
      (node (ref "D2") (pin "R6") (pinfunction "GND_R6") (pintype "power_in"))
      (node (ref "D2") (pin "R8") (pinfunction "GND_R8") (pintype "power_in"))
      (node (ref "D2") (pin "R9") (pinfunction "GND_R9") (pintype "power_in"))
      (node (ref "D2") (pin "T1") (pinfunction "GND_T1") (pintype "power_in"))
      (node (ref "D2") (pin "T10") (pinfunction "GND_T10") (pintype "power_in"))
      (node (ref "D2") (pin "T12") (pinfunction "GND_T12") (pintype "power_in"))
      (node (ref "D2") (pin "T14") (pinfunction "GND_T14") (pintype "power_in"))
      (node (ref "D2") (pin "T15") (pinfunction "GND_T15") (pintype "power_in"))
      (node (ref "D2") (pin "T16") (pinfunction "GND_T16") (pintype "power_in"))
      (node (ref "D2") (pin "T18") (pinfunction "GND_T18") (pintype "power_in"))
      (node (ref "D2") (pin "T2") (pinfunction "GND_T2") (pintype "power_in"))
      (node (ref "D2") (pin "T20") (pinfunction "GND_T20") (pintype "power_in"))
      (node (ref "D2") (pin "T27") (pinfunction "GND_T27") (pintype "power_in"))
      (node (ref "D2") (pin "T5") (pinfunction "GND_T5") (pintype "power_in"))
      (node (ref "D2") (pin "T7") (pinfunction "GND_T7") (pintype "power_in"))
      (node (ref "D2") (pin "U11") (pinfunction "GND_U11") (pintype "power_in"))
      (node (ref "D2") (pin "U13") (pinfunction "GND_U13") (pintype "power_in"))
      (node (ref "D2") (pin "U15") (pinfunction "GND_U15") (pintype "power_in"))
      (node (ref "D2") (pin "U17") (pinfunction "GND_U17") (pintype "power_in"))
      (node (ref "D2") (pin "U22") (pinfunction "GND_U22") (pintype "power_in"))
      (node (ref "D2") (pin "U24") (pinfunction "GND_U24") (pintype "power_in"))
      (node (ref "D2") (pin "U29") (pinfunction "GND_U29") (pintype "power_in"))
      (node (ref "D2") (pin "U3") (pinfunction "GND_U3") (pintype "power_in"))
      (node (ref "D2") (pin "U4") (pinfunction "GND_U4") (pintype "power_in"))
      (node (ref "D2") (pin "U6") (pinfunction "GND_U6") (pintype "power_in"))
      (node (ref "D2") (pin "U9") (pinfunction "GND_U9") (pintype "power_in"))
      (node (ref "D2") (pin "V1") (pinfunction "GND_V1") (pintype "power_in"))
      (node (ref "D2") (pin "V10") (pinfunction "GND_V10") (pintype "power_in"))
      (node (ref "D2") (pin "V12") (pinfunction "GND_V12") (pintype "power_in"))
      (node (ref "D2") (pin "V14") (pinfunction "GND_V14") (pintype "power_in"))
      (node (ref "D2") (pin "V19") (pinfunction "GND_V19") (pintype "power_in"))
      (node (ref "D2") (pin "V2") (pinfunction "GND_V2") (pintype "power_in"))
      (node (ref "D2") (pin "V21") (pinfunction "GND_V21") (pintype "power_in"))
      (node (ref "D2") (pin "V5") (pinfunction "GND_V5") (pintype "power_in"))
      (node (ref "D2") (pin "V7") (pinfunction "GND_V7") (pintype "power_in"))
      (node (ref "D2") (pin "W11") (pinfunction "GND_W11") (pintype "power_in"))
      (node (ref "D2") (pin "W13") (pinfunction "GND_W13") (pintype "power_in"))
      (node (ref "D2") (pin "W18") (pinfunction "GND_W18") (pintype "power_in"))
      (node (ref "D2") (pin "W28") (pinfunction "GND_W28") (pintype "power_in"))
      (node (ref "D2") (pin "W3") (pinfunction "GND_W3") (pintype "power_in"))
      (node (ref "D2") (pin "W4") (pinfunction "GND_W4") (pintype "power_in"))
      (node (ref "D2") (pin "W6") (pinfunction "GND_W6") (pintype "power_in"))
      (node (ref "D2") (pin "W9") (pinfunction "GND_W9") (pintype "power_in"))
      (node (ref "D2") (pin "Y1") (pinfunction "GND_Y1") (pintype "power_in"))
      (node (ref "D2") (pin "Y10") (pinfunction "GND_Y10") (pintype "power_in"))
      (node (ref "D2") (pin "Y12") (pinfunction "GND_Y12") (pintype "power_in"))
      (node (ref "D2") (pin "Y14") (pinfunction "GND_Y14") (pintype "power_in"))
      (node (ref "D2") (pin "Y15") (pinfunction "GND_Y15") (pintype "power_in"))
      (node (ref "D2") (pin "Y2") (pinfunction "GND_Y2") (pintype "power_in"))
      (node (ref "D2") (pin "Y20") (pinfunction "GND_Y20") (pintype "power_in"))
      (node (ref "D2") (pin "Y25") (pinfunction "GND_Y25") (pintype "power_in"))
      (node (ref "D2") (pin "Y30") (pinfunction "GND_Y30") (pintype "power_in"))
      (node (ref "D2") (pin "Y5") (pinfunction "GND_Y5") (pintype "power_in"))
      (node (ref "D2") (pin "Y7") (pinfunction "GND_Y7") (pintype "power_in"))
      (node (ref "D2") (pin "Y8") (pinfunction "GND_Y8") (pintype "power_in"))
    )
    (net (code "4") (name "VCC1P1") (class "Default")
      (node (ref "C113") (pin "2") (pinfunction "-_2") (pintype "passive"))
      (node (ref "C114") (pin "2") (pinfunction "-_2") (pintype "passive"))
      (node (ref "C115") (pin "2") (pinfunction "-_2") (pintype "passive"))
      (node (ref "C116") (pin "2") (pinfunction "-_2") (pintype "passive"))
      (node (ref "C117") (pin "2") (pinfunction "-_2") (pintype "passive"))
      (node (ref "C118") (pin "2") (pinfunction "-_2") (pintype "passive"))
      (node (ref "C119") (pin "2") (pinfunction "-_2") (pintype "passive"))
      (node (ref "C120") (pin "2") (pinfunction "-_2") (pintype "passive"))
      (node (ref "C127") (pin "2") (pinfunction "-_2") (pintype "passive"))
      (node (ref "C128") (pin "2") (pinfunction "-_2") (pintype "passive"))
      (node (ref "C129") (pin "2") (pinfunction "-_2") (pintype "passive"))
      (node (ref "C130") (pin "2") (pinfunction "-_2") (pintype "passive"))
      (node (ref "C131") (pin "2") (pinfunction "-_2") (pintype "passive"))
      (node (ref "C132") (pin "2") (pinfunction "-_2") (pintype "passive"))
      (node (ref "C133") (pin "2") (pinfunction "-_2") (pintype "passive"))
      (node (ref "C134") (pin "2") (pinfunction "-_2") (pintype "passive"))
      (node (ref "C146") (pin "2") (pinfunction "-_2") (pintype "passive"))
      (node (ref "C147") (pin "2") (pinfunction "-_2") (pintype "passive"))
      (node (ref "C148") (pin "2") (pinfunction "-_2") (pintype "passive"))
      (node (ref "C149") (pin "2") (pinfunction "-_2") (pintype "passive"))
      (node (ref "C150") (pin "2") (pinfunction "-_2") (pintype "passive"))
      (node (ref "C151") (pin "2") (pinfunction "-_2") (pintype "passive"))
      (node (ref "C152") (pin "2") (pinfunction "-_2") (pintype "passive"))
      (node (ref "C153") (pin "2") (pinfunction "-_2") (pintype "passive"))
      (node (ref "C168") (pin "1") (pinfunction "+_1") (pintype "passive"))
      (node (ref "C169") (pin "1") (pinfunction "+_1") (pintype "passive"))
      (node (ref "C170") (pin "1") (pinfunction "+_1") (pintype "passive"))
      (node (ref "C171") (pin "1") (pinfunction "+_1") (pintype "passive"))
      (node (ref "C172") (pin "1") (pinfunction "+_1") (pintype "passive"))
      (node (ref "C173") (pin "1") (pinfunction "+_1") (pintype "passive"))
      (node (ref "C174") (pin "1") (pinfunction "+_1") (pintype "passive"))
      (node (ref "C180") (pin "1") (pinfunction "+_1") (pintype "passive"))
      (node (ref "C181") (pin "1") (pinfunction "+_1") (pintype "passive"))
      (node (ref "C182") (pin "1") (pinfunction "+_1") (pintype "passive"))
      (node (ref "C183") (pin "1") (pinfunction "+_1") (pintype "passive"))
      (node (ref "C184") (pin "1") (pinfunction "+_1") (pintype "passive"))
      (node (ref "C185") (pin "1") (pinfunction "+_1") (pintype "passive"))
      (node (ref "C186") (pin "1") (pinfunction "+_1") (pintype "passive"))
      (node (ref "C187") (pin "1") (pinfunction "+_1") (pintype "passive"))
      (node (ref "C189") (pin "1") (pinfunction "+_1") (pintype "passive"))
      (node (ref "C190") (pin "1") (pinfunction "+_1") (pintype "passive"))
      (node (ref "C191") (pin "1") (pinfunction "+_1") (pintype "passive"))
      (node (ref "C192") (pin "1") (pinfunction "+_1") (pintype "passive"))
      (node (ref "C193") (pin "1") (pinfunction "+_1") (pintype "passive"))
      (node (ref "C199") (pin "2") (pinfunction "-_2") (pintype "passive"))
      (node (ref "C200") (pin "2") (pinfunction "-_2") (pintype "passive"))
      (node (ref "C201") (pin "2") (pinfunction "-_2") (pintype "passive"))
      (node (ref "C202") (pin "1") (pinfunction "+_1") (pintype "passive"))
      (node (ref "C203") (pin "1") (pinfunction "+_1") (pintype "passive"))
      (node (ref "C204") (pin "1") (pinfunction "+_1") (pintype "passive"))
      (node (ref "C205") (pin "1") (pinfunction "+_1") (pintype "passive"))
      (node (ref "C210") (pin "2") (pinfunction "-_2") (pintype "passive"))
      (node (ref "C211") (pin "2") (pinfunction "-_2") (pintype "passive"))
      (node (ref "C212") (pin "2") (pinfunction "-_2") (pintype "passive"))
      (node (ref "C213") (pin "2") (pinfunction "-_2") (pintype "passive"))
      (node (ref "C214") (pin "2") (pinfunction "-_2") (pintype "passive"))
      (node (ref "C215") (pin "2") (pinfunction "-_2") (pintype "passive"))
      (node (ref "C216") (pin "2") (pinfunction "-_2") (pintype "passive"))
      (node (ref "C94") (pin "1") (pinfunction "+_1") (pintype "passive"))
      (node (ref "D2") (pin "L16") (pinfunction "VCC_HPS_L16") (pintype "power_in"))
      (node (ref "D2") (pin "L18") (pinfunction "VCC_HPS_L18") (pintype "power_in"))
      (node (ref "D2") (pin "L20") (pinfunction "VCC_HPS_L20") (pintype "power_in"))
      (node (ref "D2") (pin "M11") (pinfunction "VCC_M11") (pintype "power_in"))
      (node (ref "D2") (pin "M13") (pinfunction "VCC_M13") (pintype "power_in"))
      (node (ref "D2") (pin "M15") (pinfunction "VCC_HPS_M15") (pintype "power_in"))
      (node (ref "D2") (pin "M9") (pinfunction "VCC_M9") (pintype "power_in"))
      (node (ref "D2") (pin "N10") (pinfunction "VCC_N10") (pintype "power_in"))
      (node (ref "D2") (pin "N12") (pinfunction "VCC_N12") (pintype "power_in"))
      (node (ref "D2") (pin "N14") (pinfunction "VCC_N14") (pintype "power_in"))
      (node (ref "D2") (pin "N20") (pinfunction "VCC_HPS_N20") (pintype "power_in"))
      (node (ref "D2") (pin "P11") (pinfunction "VCC_P11") (pintype "power_in"))
      (node (ref "D2") (pin "P13") (pinfunction "VCC_P13") (pintype "power_in"))
      (node (ref "D2") (pin "P15") (pinfunction "VCC_HPS_P15") (pintype "power_in"))
      (node (ref "D2") (pin "P17") (pinfunction "VCC_HPS_P17") (pintype "power_in"))
      (node (ref "D2") (pin "P19") (pinfunction "VCC_HPS_P19") (pintype "power_in"))
      (node (ref "D2") (pin "R10") (pinfunction "VCC_R10") (pintype "power_in"))
      (node (ref "D2") (pin "R12") (pinfunction "VCC_R12") (pintype "power_in"))
      (node (ref "D2") (pin "R14") (pinfunction "VCC_R14") (pintype "power_in"))
      (node (ref "D2") (pin "R16") (pinfunction "VCC_HPS_R16") (pintype "power_in"))
      (node (ref "D2") (pin "T11") (pinfunction "VCC_T11") (pintype "power_in"))
      (node (ref "D2") (pin "T13") (pinfunction "VCC_T13") (pintype "power_in"))
      (node (ref "D2") (pin "T17") (pinfunction "VCC_HPS_T17") (pintype "power_in"))
      (node (ref "D2") (pin "T19") (pinfunction "VCC_HPS_T19") (pintype "power_in"))
      (node (ref "D2") (pin "U10") (pinfunction "VCC_U10") (pintype "power_in"))
      (node (ref "D2") (pin "U12") (pinfunction "VCC_U12") (pintype "power_in"))
      (node (ref "D2") (pin "U14") (pinfunction "VCC_U14") (pintype "power_in"))
      (node (ref "D2") (pin "U16") (pinfunction "VCC_HPS_U16") (pintype "power_in"))
      (node (ref "D2") (pin "U18") (pinfunction "VCC_HPS_U18") (pintype "power_in"))
      (node (ref "D2") (pin "U21") (pinfunction "VCC_U21") (pintype "power_in"))
      (node (ref "D2") (pin "V11") (pinfunction "VCC_V11") (pintype "power_in"))
      (node (ref "D2") (pin "V13") (pinfunction "VCC_V13") (pintype "power_in"))
      (node (ref "D2") (pin "V15") (pinfunction "VCC_V15") (pintype "power_in"))
      (node (ref "D2") (pin "W10") (pinfunction "VCC_W10") (pintype "power_in"))
      (node (ref "D2") (pin "W12") (pinfunction "VCC_W12") (pintype "power_in"))
      (node (ref "D2") (pin "W14") (pinfunction "VCC_W14") (pintype "power_in"))
      (node (ref "D2") (pin "Y11") (pinfunction "VCC_Y11") (pintype "power_in"))
      (node (ref "D2") (pin "Y13") (pinfunction "VCC_Y13") (pintype "power_in"))
      (node (ref "D2") (pin "Y9") (pinfunction "VCC_Y9") (pintype "power_in"))
      (node (ref "L2") (pin "2") (pinfunction "2_2") (pintype "passive"))
    )
    (net (code "5") (name "VCC1P5_DDR3") (class "Default")
      (node (ref "C107") (pin "2") (pinfunction "-_2") (pintype "passive"))
      (node (ref "C108") (pin "2") (pinfunction "-_2") (pintype "passive"))
      (node (ref "C109") (pin "2") (pinfunction "-_2") (pintype "passive"))
      (node (ref "C110") (pin "2") (pinfunction "-_2") (pintype "passive"))
      (node (ref "C111") (pin "2") (pinfunction "-_2") (pintype "passive"))
      (node (ref "C175") (pin "1") (pinfunction "+_1") (pintype "passive"))
      (node (ref "C194") (pin "2") (pinfunction "-_2") (pintype "passive"))
      (node (ref "C195") (pin "2") (pinfunction "-_2") (pintype "passive"))
      (node (ref "C196") (pin "2") (pinfunction "-_2") (pintype "passive"))
      (node (ref "C197") (pin "2") (pinfunction "-_2") (pintype "passive"))
      (node (ref "C198") (pin "2") (pinfunction "-_2") (pintype "passive"))
      (node (ref "C220") (pin "2") (pinfunction "-_2") (pintype "passive"))
      (node (ref "C221") (pin "2") (pinfunction "-_2") (pintype "passive"))
      (node (ref "C222") (pin "2") (pinfunction "-_2") (pintype "passive"))
      (node (ref "C223") (pin "2") (pinfunction "-_2") (pintype "passive"))
      (node (ref "C224") (pin "2") (pinfunction "-_2") (pintype "passive"))
      (node (ref "C225") (pin "2") (pinfunction "-_2") (pintype "passive"))
      (node (ref "C227") (pin "1") (pinfunction "+_1") (pintype "passive"))
      (node (ref "C228") (pin "1") (pinfunction "+_1") (pintype "passive"))
      (node (ref "C229") (pin "2") (pinfunction "-_2") (pintype "passive"))
      (node (ref "C230") (pin "2") (pinfunction "-_2") (pintype "passive"))
      (node (ref "C231") (pin "2") (pinfunction "-_2") (pintype "passive"))
      (node (ref "C236") (pin "2") (pinfunction "-_2") (pintype "passive"))
      (node (ref "C237") (pin "2") (pinfunction "-_2") (pintype "passive"))
      (node (ref "C238") (pin "2") (pinfunction "-_2") (pintype "passive"))
      (node (ref "C239") (pin "2") (pinfunction "-_2") (pintype "passive"))
      (node (ref "C240") (pin "2") (pinfunction "-_2") (pintype "passive"))
      (node (ref "C241") (pin "2") (pinfunction "-_2") (pintype "passive"))
      (node (ref "C246") (pin "1") (pinfunction "+_1") (pintype "passive"))
      (node (ref "C247") (pin "1") (pinfunction "+_1") (pintype "passive"))
      (node (ref "C248") (pin "2") (pinfunction "-_2") (pintype "passive"))
      (node (ref "C249") (pin "2") (pinfunction "-_2") (pintype "passive"))
      (node (ref "C250") (pin "2") (pinfunction "-_2") (pintype "passive"))
      (node (ref "D2") (pin "AA17") (pinfunction "VCCIO4A_AA17") (pintype "power_in"))
      (node (ref "D2") (pin "AB14") (pinfunction "VCCIO3B_AB14") (pintype "power_in"))
      (node (ref "D2") (pin "AC21") (pinfunction "VCCIO4A_AC21") (pintype "power_in"))
      (node (ref "D2") (pin "AD13") (pinfunction "VCCIO3B_AD13") (pintype "power_in"))
      (node (ref "D2") (pin "AD18") (pinfunction "VCCIO4A_AD18") (pintype "power_in"))
      (node (ref "D2") (pin "AE15") (pinfunction "VCCIO3B_AE15") (pintype "power_in"))
      (node (ref "D2") (pin "AE25") (pinfunction "VCCIO4A_AE25") (pintype "power_in"))
      (node (ref "D2") (pin "AF22") (pinfunction "VCCIO4A_AF22") (pintype "power_in"))
      (node (ref "D2") (pin "AG19") (pinfunction "VCCIO4A_AG19") (pintype "power_in"))
      (node (ref "D2") (pin "AH16") (pinfunction "VCCIO4A_AH16") (pintype "power_in"))
      (node (ref "D2") (pin "AH26") (pinfunction "VCCIO4A_AH26") (pintype "power_in"))
      (node (ref "D2") (pin "AJ13") (pinfunction "VCCIO3B_AJ13") (pintype "power_in"))
      (node (ref "D2") (pin "AJ23") (pinfunction "VCCIO4A_AJ23") (pintype "power_in"))
      (node (ref "D2") (pin "AJ8") (pinfunction "VCCIO3B_AJ8") (pintype "power_in"))
      (node (ref "D2") (pin "AK10") (pinfunction "VCCIO3B_AK10") (pintype "power_in"))
      (node (ref "D2") (pin "AK20") (pinfunction "VCCIO4A_AK20") (pintype "power_in"))
      (node (ref "D2") (pin "D28") (pinfunction "VCCIO6A_HPS_D28") (pintype "power_in"))
      (node (ref "D2") (pin "G29") (pinfunction "VCCIO6A_HPS_G29") (pintype "power_in"))
      (node (ref "D2") (pin "H26") (pinfunction "VCCIO6A_HPS_H26") (pintype "power_in"))
      (node (ref "D2") (pin "K24") (pinfunction "VCCIO6A_HPS_K24") (pintype "power_in"))
      (node (ref "D2") (pin "K30") (pinfunction "VCCIO6A_HPS_K30") (pintype "power_in"))
      (node (ref "D2") (pin "L27") (pinfunction "VCCIO6A_HPS_L27") (pintype "power_in"))
      (node (ref "D2") (pin "M24") (pinfunction "VCCIO6A_HPS_M24") (pintype "power_in"))
      (node (ref "D2") (pin "N21") (pinfunction "VCCIO6A_HPS_N21") (pintype "power_in"))
      (node (ref "D2") (pin "P23") (pinfunction "VCCIO6B_HPS_P23") (pintype "power_in"))
      (node (ref "D2") (pin "P28") (pinfunction "VCCIO6B_HPS_P28") (pintype "power_in"))
      (node (ref "D2") (pin "R25") (pinfunction "VCCIO6B_HPS_R25") (pintype "power_in"))
      (node (ref "D2") (pin "T22") (pinfunction "VCCIO6B_HPS_T22") (pintype "power_in"))
      (node (ref "D2") (pin "U19") (pinfunction "VCCIO6B_HPS_U19") (pintype "power_in"))
      (node (ref "D2") (pin "V26") (pinfunction "VCCIO6B_HPS_V26") (pintype "power_in"))
    )
    (net (code "6") (name "VCC2P5") (class "Default")
      (node (ref "C112") (pin "1") (pinfunction "+_1") (pintype "passive"))
      (node (ref "C121") (pin "2") (pinfunction "-_2") (pintype "passive"))
      (node (ref "C122") (pin "2") (pinfunction "-_2") (pintype "passive"))
      (node (ref "C135") (pin "2") (pinfunction "-_2") (pintype "passive"))
      (node (ref "C136") (pin "2") (pinfunction "-_2") (pintype "passive"))
      (node (ref "C137") (pin "1") (pinfunction "+_1") (pintype "passive"))
      (node (ref "C142") (pin "2") (pinfunction "-_2") (pintype "passive"))
      (node (ref "C143") (pin "2") (pinfunction "-_2") (pintype "passive"))
      (node (ref "C144") (pin "2") (pinfunction "-_2") (pintype "passive"))
      (node (ref "C145") (pin "2") (pinfunction "-_2") (pintype "passive"))
      (node (ref "C154") (pin "1") (pinfunction "+_1") (pintype "passive"))
      (node (ref "C164") (pin "2") (pinfunction "-_2") (pintype "passive"))
      (node (ref "C165") (pin "2") (pinfunction "-_2") (pintype "passive"))
      (node (ref "C166") (pin "2") (pinfunction "-_2") (pintype "passive"))
      (node (ref "C206") (pin "2") (pinfunction "-_2") (pintype "passive"))
      (node (ref "C207") (pin "2") (pinfunction "-_2") (pintype "passive"))
      (node (ref "C259") (pin "2") (pinfunction "-_2") (pintype "passive"))
      (node (ref "C260") (pin "2") (pinfunction "-_2") (pintype "passive"))
      (node (ref "C261") (pin "2") (pinfunction "-_2") (pintype "passive"))
      (node (ref "C262") (pin "2") (pinfunction "-_2") (pintype "passive"))
      (node (ref "C263") (pin "2") (pinfunction "-_2") (pintype "passive"))
      (node (ref "C264") (pin "2") (pinfunction "-_2") (pintype "passive"))
      (node (ref "C265") (pin "2") (pinfunction "-_2") (pintype "passive"))
      (node (ref "C266") (pin "2") (pinfunction "-_2") (pintype "passive"))
      (node (ref "C87") (pin "1") (pinfunction "+_1") (pintype "passive"))
      (node (ref "D2") (pin "A7") (pinfunction "VCCIO8A_A7") (pintype "power_in"))
      (node (ref "D2") (pin "AA10") (pinfunction "VCCPD3A_AA10") (pintype "power_in"))
      (node (ref "D2") (pin "AA27") (pinfunction "VCCIO5B_AA27") (pintype "power_in"))
      (node (ref "D2") (pin "AB18") (pinfunction "VCCPD3B4A_AB18") (pintype "power_in"))
      (node (ref "D2") (pin "AB20") (pinfunction "VCCPD3B4A_AB20") (pintype "power_in"))
      (node (ref "D2") (pin "AB24") (pinfunction "VCCIO5A_AB24") (pintype "power_in"))
      (node (ref "D2") (pin "AC10") (pinfunction "VCCPD3A_AC10") (pintype "power_in"))
      (node (ref "D2") (pin "AC11") (pinfunction "VCCIO3A_AC11") (pintype "power_in"))
      (node (ref "D2") (pin "AC13") (pinfunction "VCCPD3B4A_AC13") (pintype "power_in"))
      (node (ref "D2") (pin "AC15") (pinfunction "VCCPD3B4A_AC15") (pintype "power_in"))
      (node (ref "D2") (pin "AC17") (pinfunction "VCCPD3B4A_AC17") (pintype "power_in"))
      (node (ref "D2") (pin "AC19") (pinfunction "VCCPD3B4A_AC19") (pintype "power_in"))
      (node (ref "D2") (pin "AD16") (pinfunction "VCCPD3B4A_AD16") (pintype "power_in"))
      (node (ref "D2") (pin "AD28") (pinfunction "VCCIO5A_AD28") (pintype "power_in"))
      (node (ref "D2") (pin "AD8") (pinfunction "VCCIO3A_AD8") (pintype "power_in"))
      (node (ref "D2") (pin "AE21") (pinfunction "VCCPD3B4A_AE21") (pintype "power_in"))
      (node (ref "D2") (pin "AE30") (pinfunction "VCCIO5B_AE30") (pintype "power_in"))
      (node (ref "D2") (pin "AF7") (pinfunction "VCCIO3A_AF7") (pintype "power_in"))
      (node (ref "D2") (pin "AG29") (pinfunction "VCCIO5A_AG29") (pintype "power_in"))
      (node (ref "D2") (pin "AG4") (pinfunction "VCCIO3A_AG4") (pintype "power_in"))
      (node (ref "D2") (pin "B4") (pinfunction "VCCIO8A_B4") (pintype "power_in"))
      (node (ref "D2") (pin "C11") (pinfunction "VCCIO8A_C11") (pintype "power_in"))
      (node (ref "D2") (pin "D8") (pinfunction "VCCIO8A_D8") (pintype "power_in"))
      (node (ref "D2") (pin "E5") (pinfunction "VCCIO8A_E5") (pintype "power_in"))
      (node (ref "D2") (pin "F12") (pinfunction "VCCIO8A_F12") (pintype "power_in"))
      (node (ref "D2") (pin "G14") (pinfunction "VCCIO8A_G14") (pintype "power_in"))
      (node (ref "D2") (pin "G9") (pinfunction "VCCIO8A_G9") (pintype "power_in"))
      (node (ref "D2") (pin "H6") (pinfunction "VCCIO8A_H6") (pintype "power_in"))
      (node (ref "D2") (pin "J13") (pinfunction "VCCIO8A_J13") (pintype "power_in"))
      (node (ref "D2") (pin "K11") (pinfunction "VCCPD8A_K11") (pintype "power_in"))
      (node (ref "D2") (pin "K13") (pinfunction "VCCPD8A_K13") (pintype "power_in"))
      (node (ref "D2") (pin "L10") (pinfunction "VCCPD8A_L10") (pintype "power_in"))
      (node (ref "D2") (pin "L12") (pinfunction "VCCPD8A_L12") (pintype "power_in"))
      (node (ref "D2") (pin "L14") (pinfunction "VCCPD8A_L14") (pintype "power_in"))
      (node (ref "D2") (pin "M21") (pinfunction "VCCPD6A6B_HPS_M21") (pintype "power_in"))
      (node (ref "D2") (pin "N22") (pinfunction "VCCPD6A6B_HPS_N22") (pintype "power_in"))
      (node (ref "D2") (pin "P21") (pinfunction "VCCPD6A6B_HPS_P21") (pintype "power_in"))
      (node (ref "D2") (pin "R20") (pinfunction "VCCPD6A6B_HPS_R20") (pintype "power_in"))
      (node (ref "D2") (pin "R23") (pinfunction "VCCPD6A6B_HPS_R23") (pintype "power_in"))
      (node (ref "D2") (pin "U23") (pinfunction "VCCPD5B_U23") (pintype "power_in"))
      (node (ref "D2") (pin "V22") (pinfunction "VCCPD5A_V22") (pintype "power_in"))
      (node (ref "D2") (pin "V24") (pinfunction "VCCPD5A_V24") (pintype "power_in"))
      (node (ref "D2") (pin "W23") (pinfunction "VCCIO5A_W23") (pintype "power_in"))
      (node (ref "L1") (pin "2") (pinfunction "2_2") (pintype "passive"))
      (node (ref "L13") (pin "2") (pinfunction "2_2") (pintype "passive"))
      (node (ref "L3") (pin "2") (pinfunction "2_2") (pintype "passive"))
      (node (ref "L4") (pin "2") (pinfunction "2_2") (pintype "passive"))
      (node (ref "L5") (pin "1") (pinfunction "1_1") (pintype "passive"))
    )
    (net (code "7") (name "VCC3P3") (class "Default")
      (node (ref "C208") (pin "2") (pinfunction "-_2") (pintype "passive"))
      (node (ref "C209") (pin "2") (pinfunction "-_2") (pintype "passive"))
      (node (ref "C217") (pin "2") (pinfunction "-_2") (pintype "passive"))
      (node (ref "C218") (pin "2") (pinfunction "-_2") (pintype "passive"))
      (node (ref "C219") (pin "2") (pinfunction "-_2") (pintype "passive"))
      (node (ref "C226") (pin "2") (pinfunction "-_2") (pintype "passive"))
      (node (ref "C251") (pin "2") (pinfunction "-_2") (pintype "passive"))
      (node (ref "C252") (pin "2") (pinfunction "-_2") (pintype "passive"))
      (node (ref "C253") (pin "2") (pinfunction "-_2") (pintype "passive"))
      (node (ref "C254") (pin "2") (pinfunction "-_2") (pintype "passive"))
      (node (ref "C255") (pin "2") (pinfunction "-_2") (pintype "passive"))
      (node (ref "C256") (pin "2") (pinfunction "-_2") (pintype "passive"))
      (node (ref "C257") (pin "2") (pinfunction "-_2") (pintype "passive"))
      (node (ref "C258") (pin "2") (pinfunction "-_2") (pintype "passive"))
      (node (ref "D2") (pin "AA23") (pinfunction "VCCPGM_AA23") (pintype "power_in"))
      (node (ref "D2") (pin "AB10") (pinfunction "VCCPGM_AB10") (pintype "power_in"))
      (node (ref "D2") (pin "D18") (pinfunction "VCCIO7C_HPS_D18") (pintype "power_in"))
      (node (ref "D2") (pin "E15") (pinfunction "VCCIO7D_HPS_E15") (pintype "power_in"))
      (node (ref "D2") (pin "E20") (pinfunction "VCCIO7B_HPS_E20") (pintype "power_in"))
      (node (ref "D2") (pin "F22") (pinfunction "VCCIO7A_HPS_F22") (pintype "power_in"))
      (node (ref "D2") (pin "G19") (pinfunction "VCCIO7B_HPS_G19") (pintype "power_in"))
      (node (ref "D2") (pin "H16") (pinfunction "VCCIO7D_HPS_H16") (pintype "power_in"))
      (node (ref "D2") (pin "H21") (pinfunction "VCCIO7A_HPS_H21") (pintype "power_in"))
      (node (ref "D2") (pin "J11") (pinfunction "VCCPGM_J11") (pintype "power_in"))
      (node (ref "D2") (pin "J17") (pinfunction "VCCPD7C_HPS_J17") (pintype "power_in"))
      (node (ref "D2") (pin "K16") (pinfunction "VCCPD7D_HPS_K16") (pintype "power_in"))
      (node (ref "D2") (pin "K18") (pinfunction "VCCPD7B_HPS_K18") (pintype "power_in"))
      (node (ref "D2") (pin "K19") (pinfunction "VCCPD7A_HPS_K19") (pintype "power_in"))
      (node (ref "L6") (pin "1") (pinfunction "1_1") (pintype "passive"))
    )
    (net (code "8") (name "VCCAUX_2p5") (class "Default")
      (node (ref "C138") (pin "2") (pinfunction "-_2") (pintype "passive"))
      (node (ref "C139") (pin "2") (pinfunction "-_2") (pintype "passive"))
      (node (ref "C140") (pin "2") (pinfunction "-_2") (pintype "passive"))
      (node (ref "C141") (pin "2") (pinfunction "-_2") (pintype "passive"))
      (node (ref "D2") (pin "AB11") (pinfunction "VCC_AUX_AB11") (pintype "power_in"))
      (node (ref "D2") (pin "AB16") (pinfunction "VCC_AUX_AB16") (pintype "power_in"))
      (node (ref "D2") (pin "AD22") (pinfunction "VCC_AUX_AD22") (pintype "power_in"))
      (node (ref "D2") (pin "H10") (pinfunction "VCC_AUX_H10") (pintype "power_in"))
      (node (ref "D2") (pin "J16") (pinfunction "VCC_AUX_J16") (pintype "power_in"))
      (node (ref "L3") (pin "1") (pinfunction "1_1") (pintype "passive"))
    )
    (net (code "9") (name "VCCAUX_SH_2p5") (class "Default")
      (node (ref "C176") (pin "2") (pinfunction "-_2") (pintype "passive"))
      (node (ref "C177") (pin "2") (pinfunction "-_2") (pintype "passive"))
      (node (ref "C178") (pin "2") (pinfunction "-_2") (pintype "passive"))
      (node (ref "C179") (pin "2") (pinfunction "-_2") (pintype "passive"))
      (node (ref "D2") (pin "J21") (pinfunction "VCC_AUX_SHARED_J21") (pintype "power_in"))
      (node (ref "L4") (pin "1") (pinfunction "1_1") (pintype "passive"))
    )
    (net (code "10") (name "VCCA_FPLL_2p5") (class "Default")
      (node (ref "C155") (pin "2") (pinfunction "-_2") (pintype "passive"))
      (node (ref "C156") (pin "2") (pinfunction "-_2") (pintype "passive"))
      (node (ref "C157") (pin "2") (pinfunction "-_2") (pintype "passive"))
      (node (ref "C158") (pin "2") (pinfunction "-_2") (pintype "passive"))
      (node (ref "C159") (pin "2") (pinfunction "-_2") (pintype "passive"))
      (node (ref "C160") (pin "2") (pinfunction "-_2") (pintype "passive"))
      (node (ref "C161") (pin "2") (pinfunction "-_2") (pintype "passive"))
      (node (ref "C162") (pin "1") (pinfunction "+_1") (pintype "passive"))
      (node (ref "C163") (pin "1") (pinfunction "+_1") (pintype "passive"))
      (node (ref "D2") (pin "AA8") (pinfunction "VCCA_FPLL_AA8") (pintype "power_in"))
      (node (ref "D2") (pin "K9") (pinfunction "VCCA_FPLL_K9") (pintype "power_in"))
      (node (ref "D2") (pin "N7") (pinfunction "VCCA_FPLL_N7") (pintype "power_in"))
      (node (ref "D2") (pin "R7") (pinfunction "VCCA_FPLL_R7") (pintype "power_in"))
      (node (ref "D2") (pin "V8") (pinfunction "VCCA_FPLL_V8") (pintype "power_in"))
      (node (ref "D2") (pin "Y22") (pinfunction "VCCA_FPLL_Y22") (pintype "power_in"))
      (node (ref "L13") (pin "1") (pinfunction "1_1") (pintype "passive"))
    )
    (net (code "11") (name "VCCH_GXBL_2p5") (class "Default")
      (node (ref "C123") (pin "2") (pinfunction "-_2") (pintype "passive"))
      (node (ref "C124") (pin "2") (pinfunction "-_2") (pintype "passive"))
      (node (ref "C125") (pin "2") (pinfunction "-_2") (pintype "passive"))
      (node (ref "C126") (pin "2") (pinfunction "-_2") (pintype "passive"))
      (node (ref "D2") (pin "AB6") (pinfunction "VCCH_GXBL_AB6") (pintype "power_in"))
      (node (ref "D2") (pin "P6") (pinfunction "VCCH_GXBL_P6") (pintype "power_in"))
      (node (ref "D2") (pin "V6") (pinfunction "VCCH_GXBL_V6") (pintype "power_in"))
      (node (ref "L1") (pin "1") (pinfunction "1_1") (pintype "passive"))
    )
    (net (code "12") (name "VCCL_GXBL_1p1") (class "Default")
      (node (ref "C103") (pin "2") (pinfunction "-_2") (pintype "passive"))
      (node (ref "C105") (pin "2") (pinfunction "-_2") (pintype "passive"))
      (node (ref "C106") (pin "2") (pinfunction "-_2") (pintype "passive"))
      (node (ref "C70") (pin "2") (pinfunction "-_2") (pintype "passive"))
      (node (ref "D2") (pin "AA5") (pinfunction "VCCE_GXBL_AA5") (pintype "power_in"))
      (node (ref "D2") (pin "L5") (pinfunction "VCCL_GXBL_L5") (pintype "power_in"))
      (node (ref "D2") (pin "M6") (pinfunction "VCCE_GXBL_M6") (pintype "power_in"))
      (node (ref "D2") (pin "N5") (pinfunction "VCCE_GXBL_N5") (pintype "power_in"))
      (node (ref "D2") (pin "R5") (pinfunction "VCCL_GXBL_R5") (pintype "power_in"))
      (node (ref "D2") (pin "T6") (pinfunction "VCCE_GXBL_T6") (pintype "power_in"))
      (node (ref "D2") (pin "U5") (pinfunction "VCCE_GXBL_U5") (pintype "power_in"))
      (node (ref "D2") (pin "W5") (pinfunction "VCCL_GXBL_W5") (pintype "power_in"))
      (node (ref "D2") (pin "Y6") (pinfunction "VCCE_GXBL_Y6") (pintype "power_in"))
      (node (ref "L2") (pin "1") (pinfunction "1_1") (pintype "passive"))
    )
    (net (code "13") (name "VCCPLL_HPS_2p5") (class "Default")
      (node (ref "C232") (pin "2") (pinfunction "-_2") (pintype "passive"))
      (node (ref "C233") (pin "2") (pinfunction "-_2") (pintype "passive"))
      (node (ref "C234") (pin "2") (pinfunction "-_2") (pintype "passive"))
      (node (ref "C235") (pin "2") (pinfunction "-_2") (pintype "passive"))
      (node (ref "D2") (pin "L21") (pinfunction "VCCPLL_HPS_L21") (pintype "power_in"))
      (node (ref "L5") (pin "2") (pinfunction "2_2") (pintype "passive"))
    )
    (net (code "14") (name "VCCRSTCLK_HPS") (class "Default")
      (node (ref "C242") (pin "2") (pinfunction "-_2") (pintype "passive"))
      (node (ref "C243") (pin "2") (pinfunction "-_2") (pintype "passive"))
      (node (ref "C244") (pin "2") (pinfunction "-_2") (pintype "passive"))
      (node (ref "C245") (pin "2") (pinfunction "-_2") (pintype "passive"))
      (node (ref "D2") (pin "G23") (pinfunction "VCCRSTCLK_HPS_G23") (pintype "power_in"))
      (node (ref "D2") (pin "J20") (pinfunction "VCCRSTCLK_HPS_J20") (pintype "power_in"))
      (node (ref "L6") (pin "2") (pinfunction "2_2") (pintype "passive"))
    )
    (net (code "15") (name "VCC_BAT") (class "Default")
      (node (ref "C188") (pin "1") (pinfunction "+_1") (pintype "passive"))
      (node (ref "D2") (pin "H9") (pinfunction "VCCBAT_H9") (pintype "power_in"))
    )
    (net (code "16") (name "unconnected-(C229-+-Pad1)") (class "Default")
      (node (ref "C229") (pin "1") (pinfunction "+_1") (pintype "passive"))
    )
    (net (code "17") (name "unconnected-(C248-+-Pad1)") (class "Default")
      (node (ref "C248") (pin "1") (pinfunction "+_1") (pintype "passive"))
    )
  )
)
